# hedwig.net
KiCad netlist of a schematic drawn in EAGLE
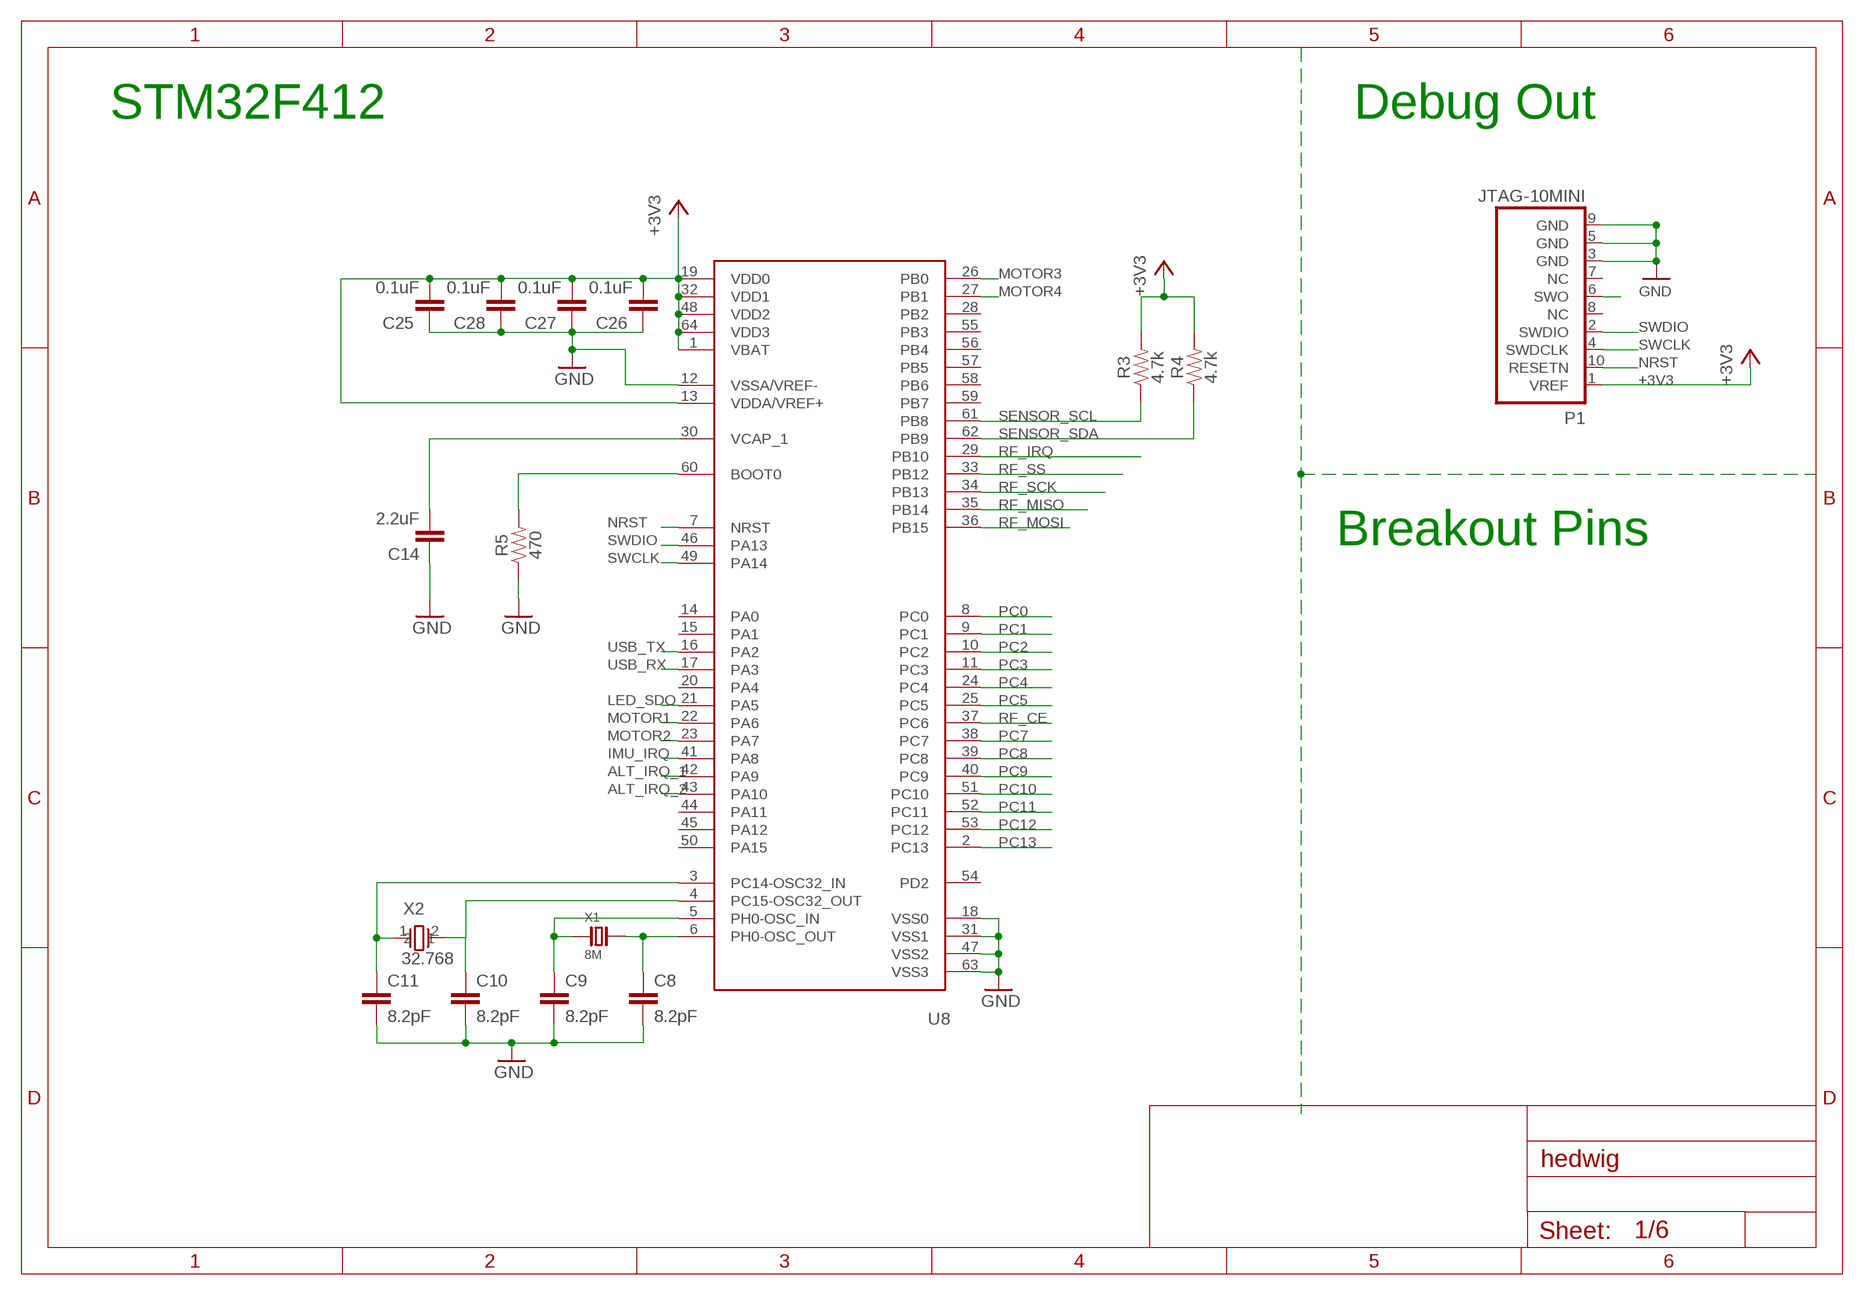
[diagram p0: schematic, sheet 1]
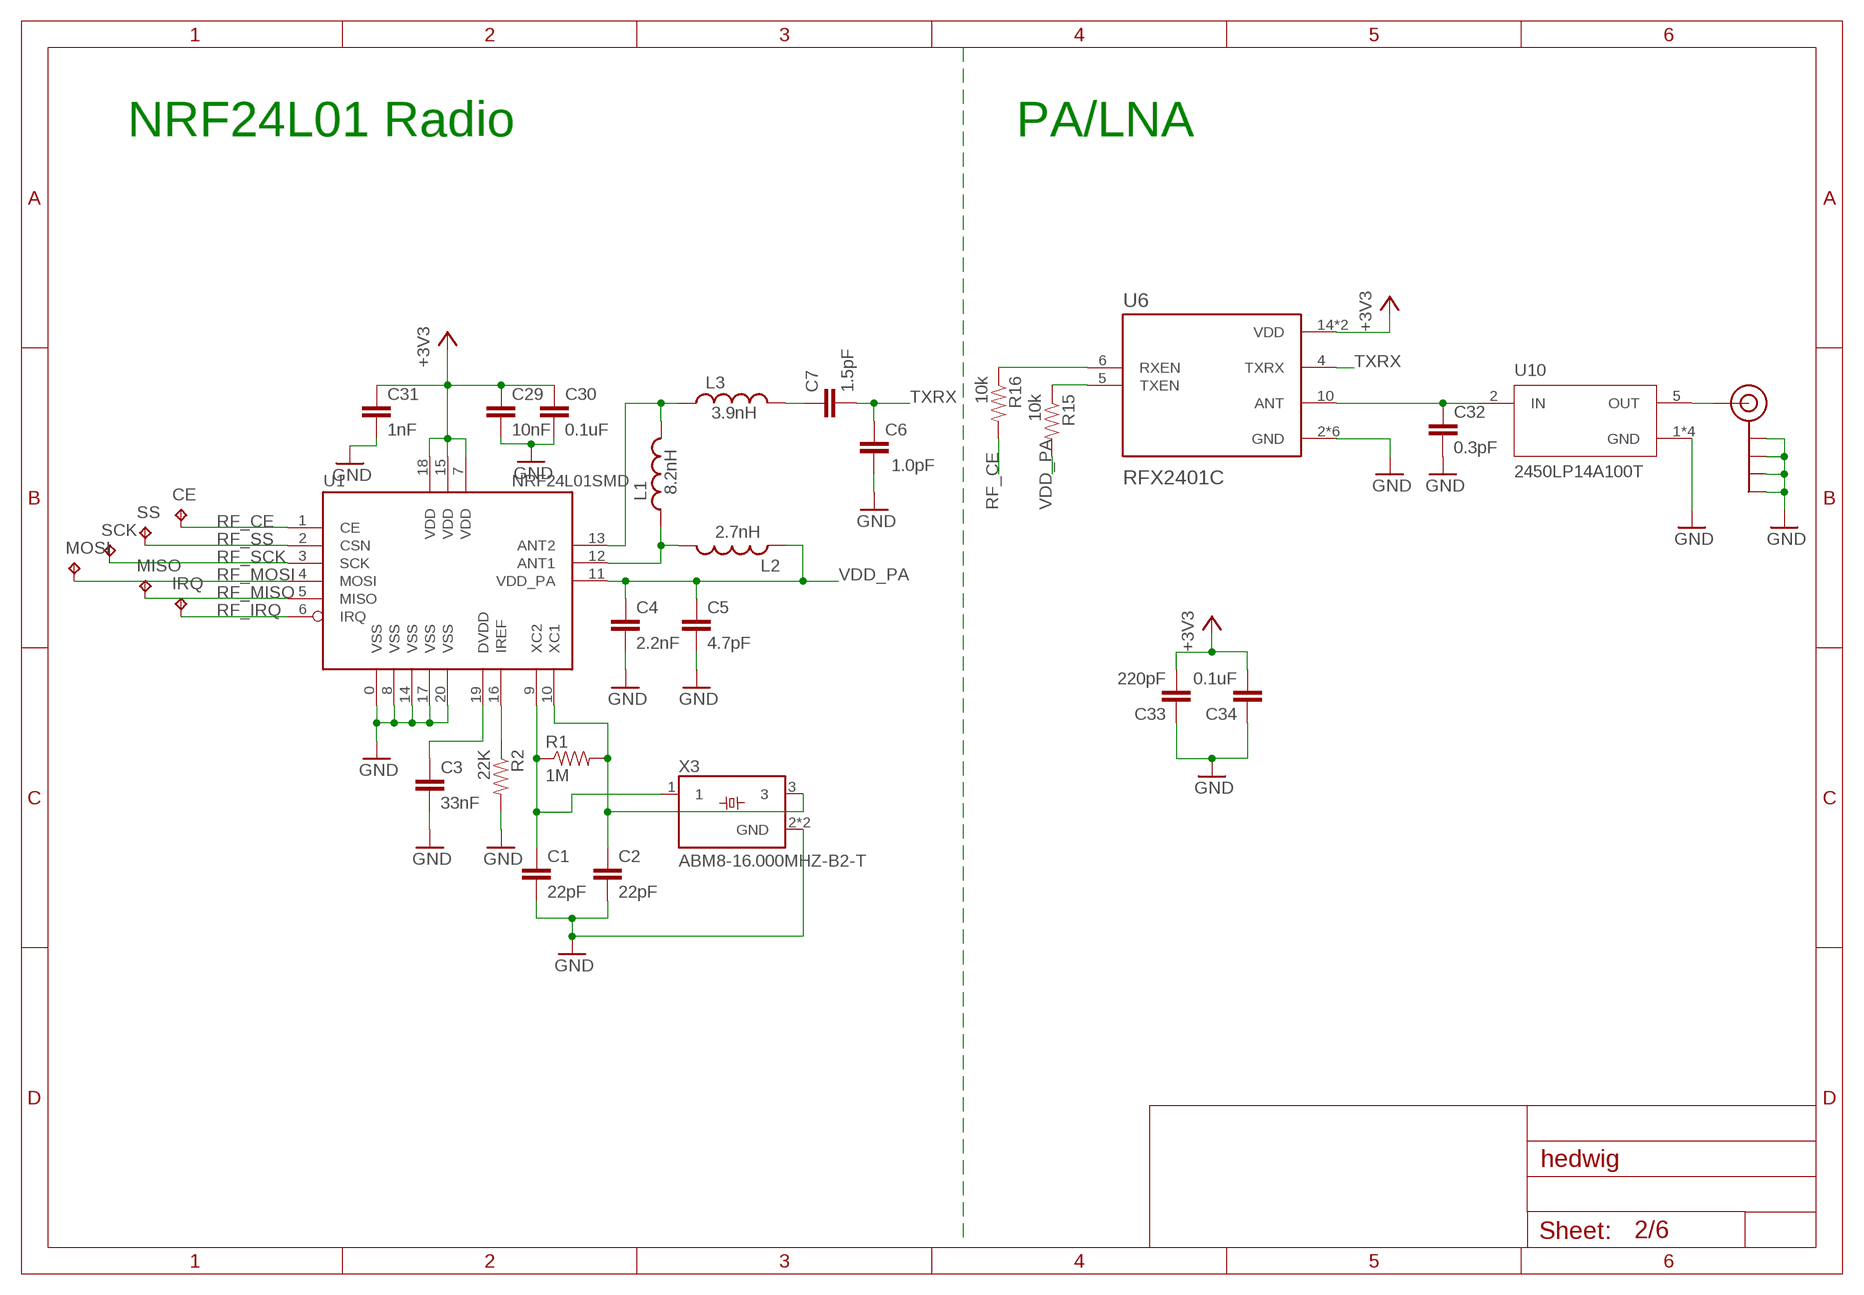
[diagram p1: schematic, sheet 2]
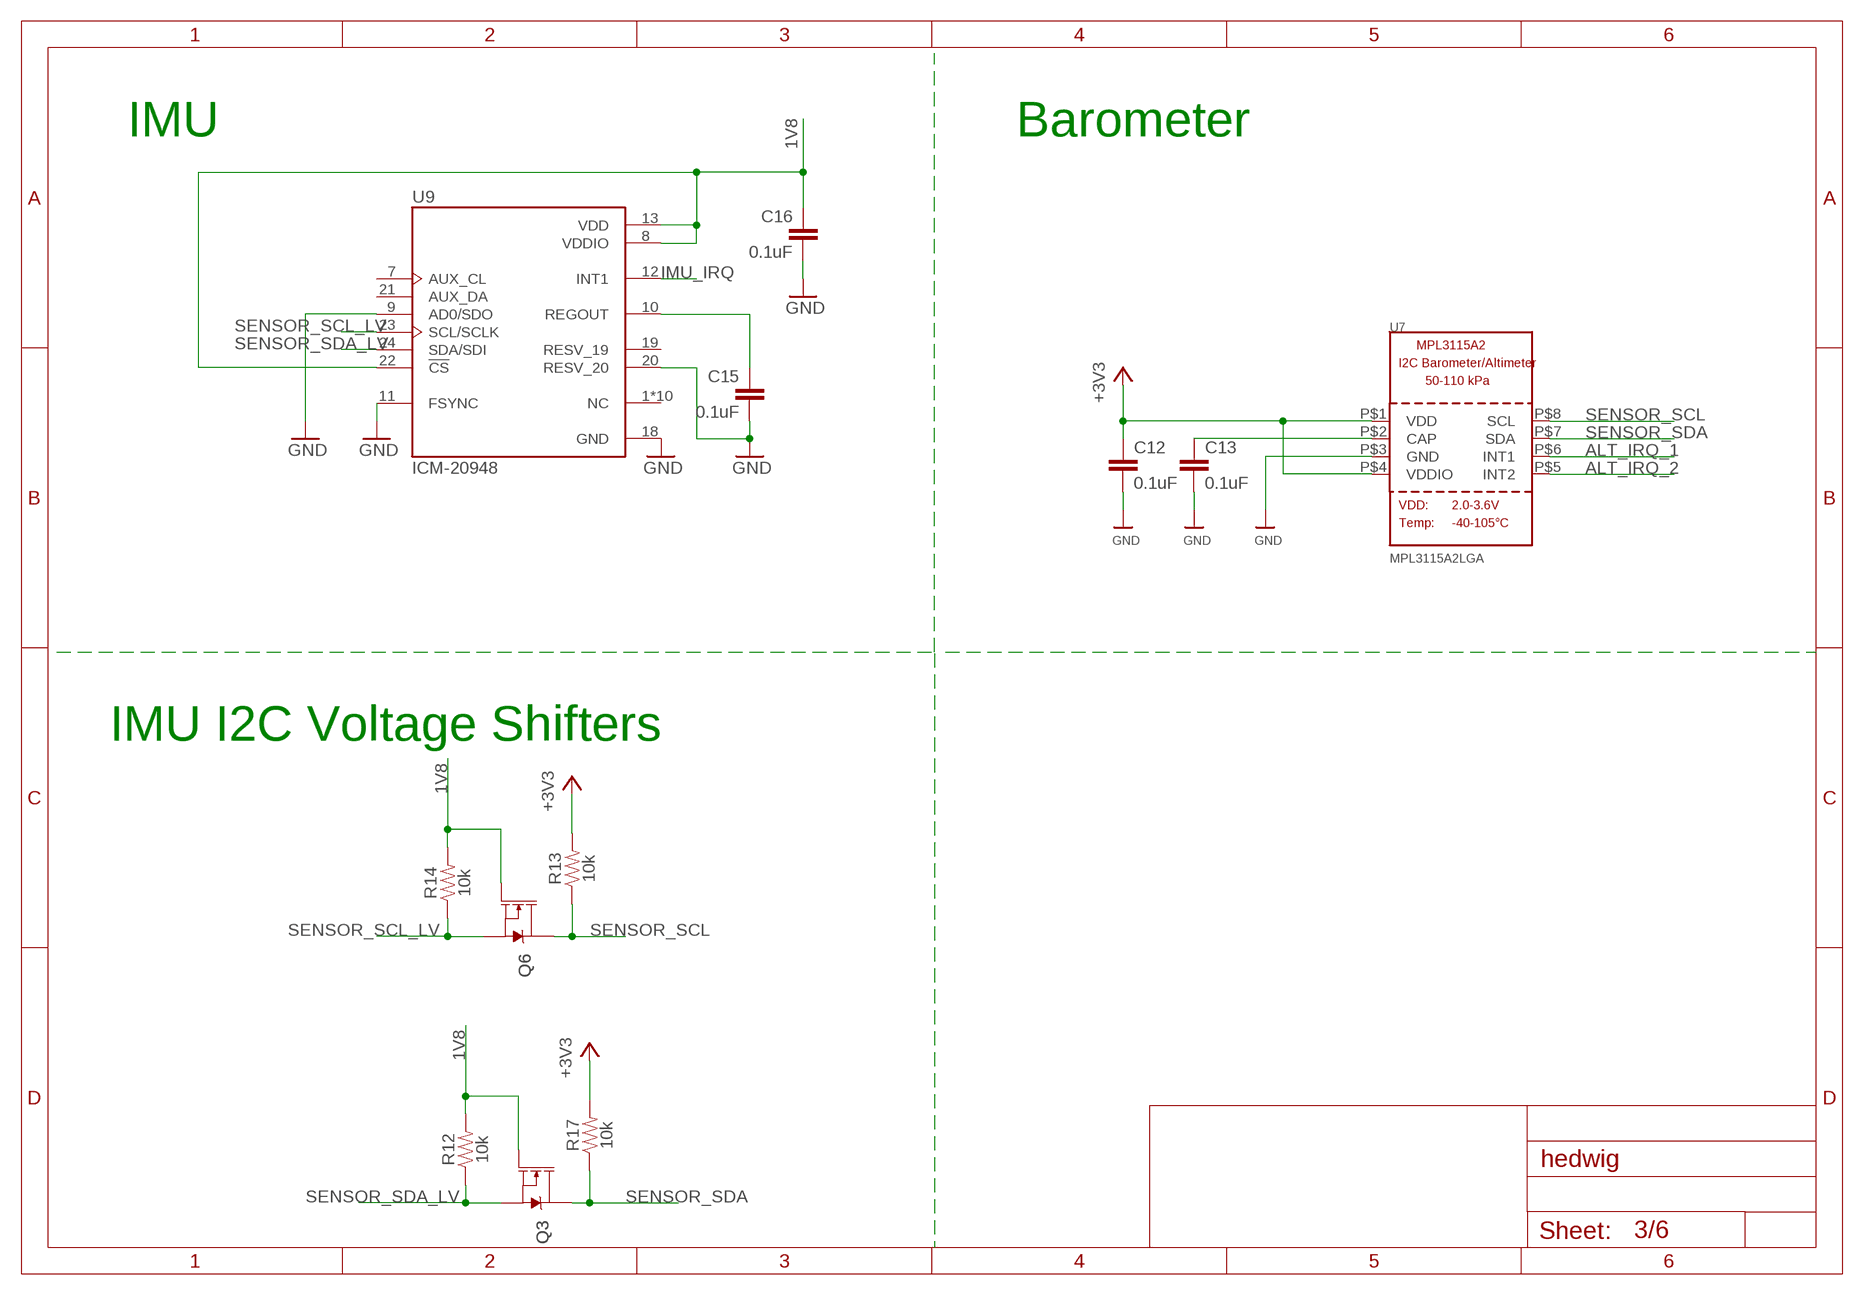
[diagram p2: schematic, sheet 3]
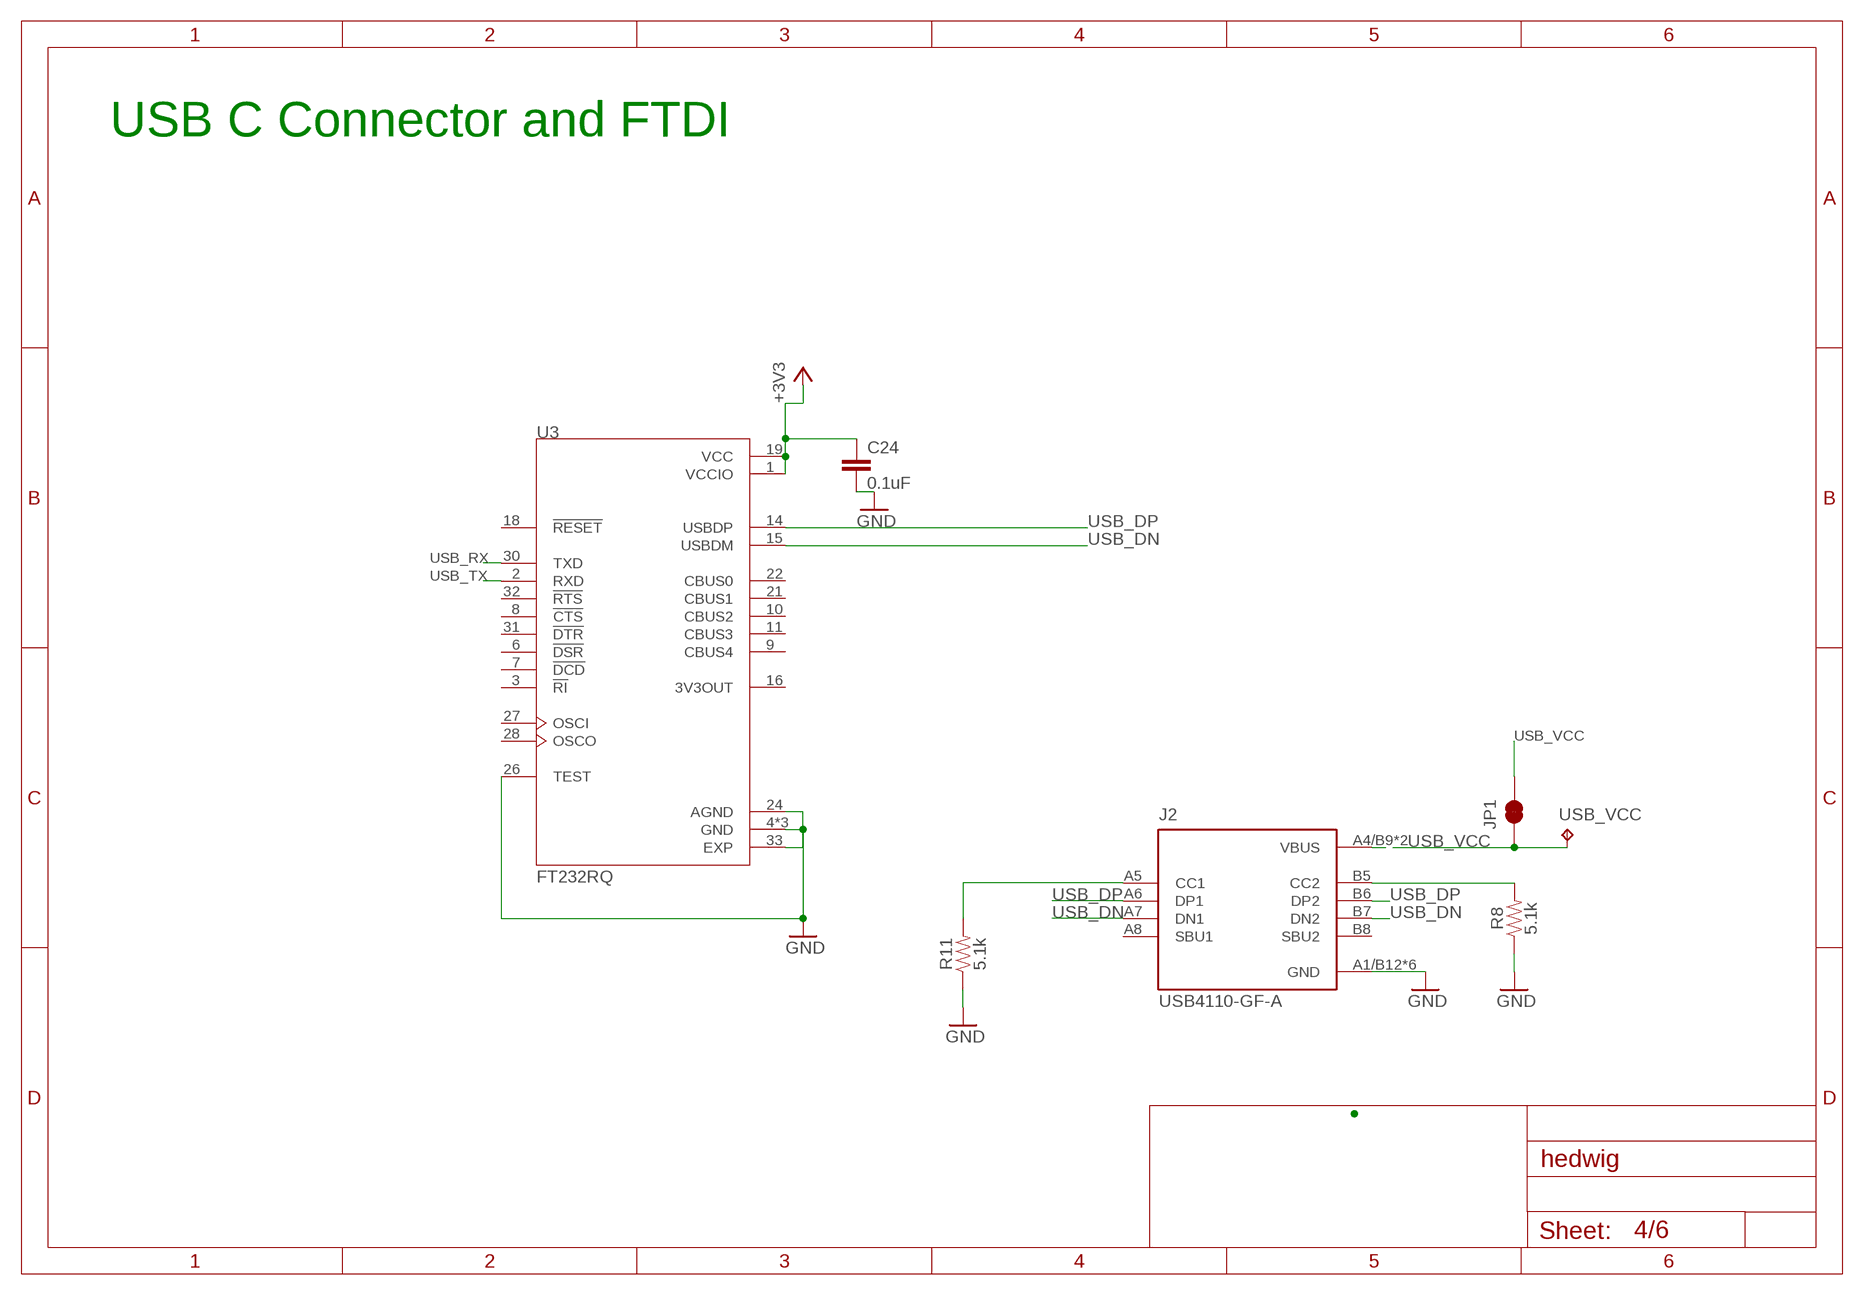
[diagram p3: schematic, sheet 4]
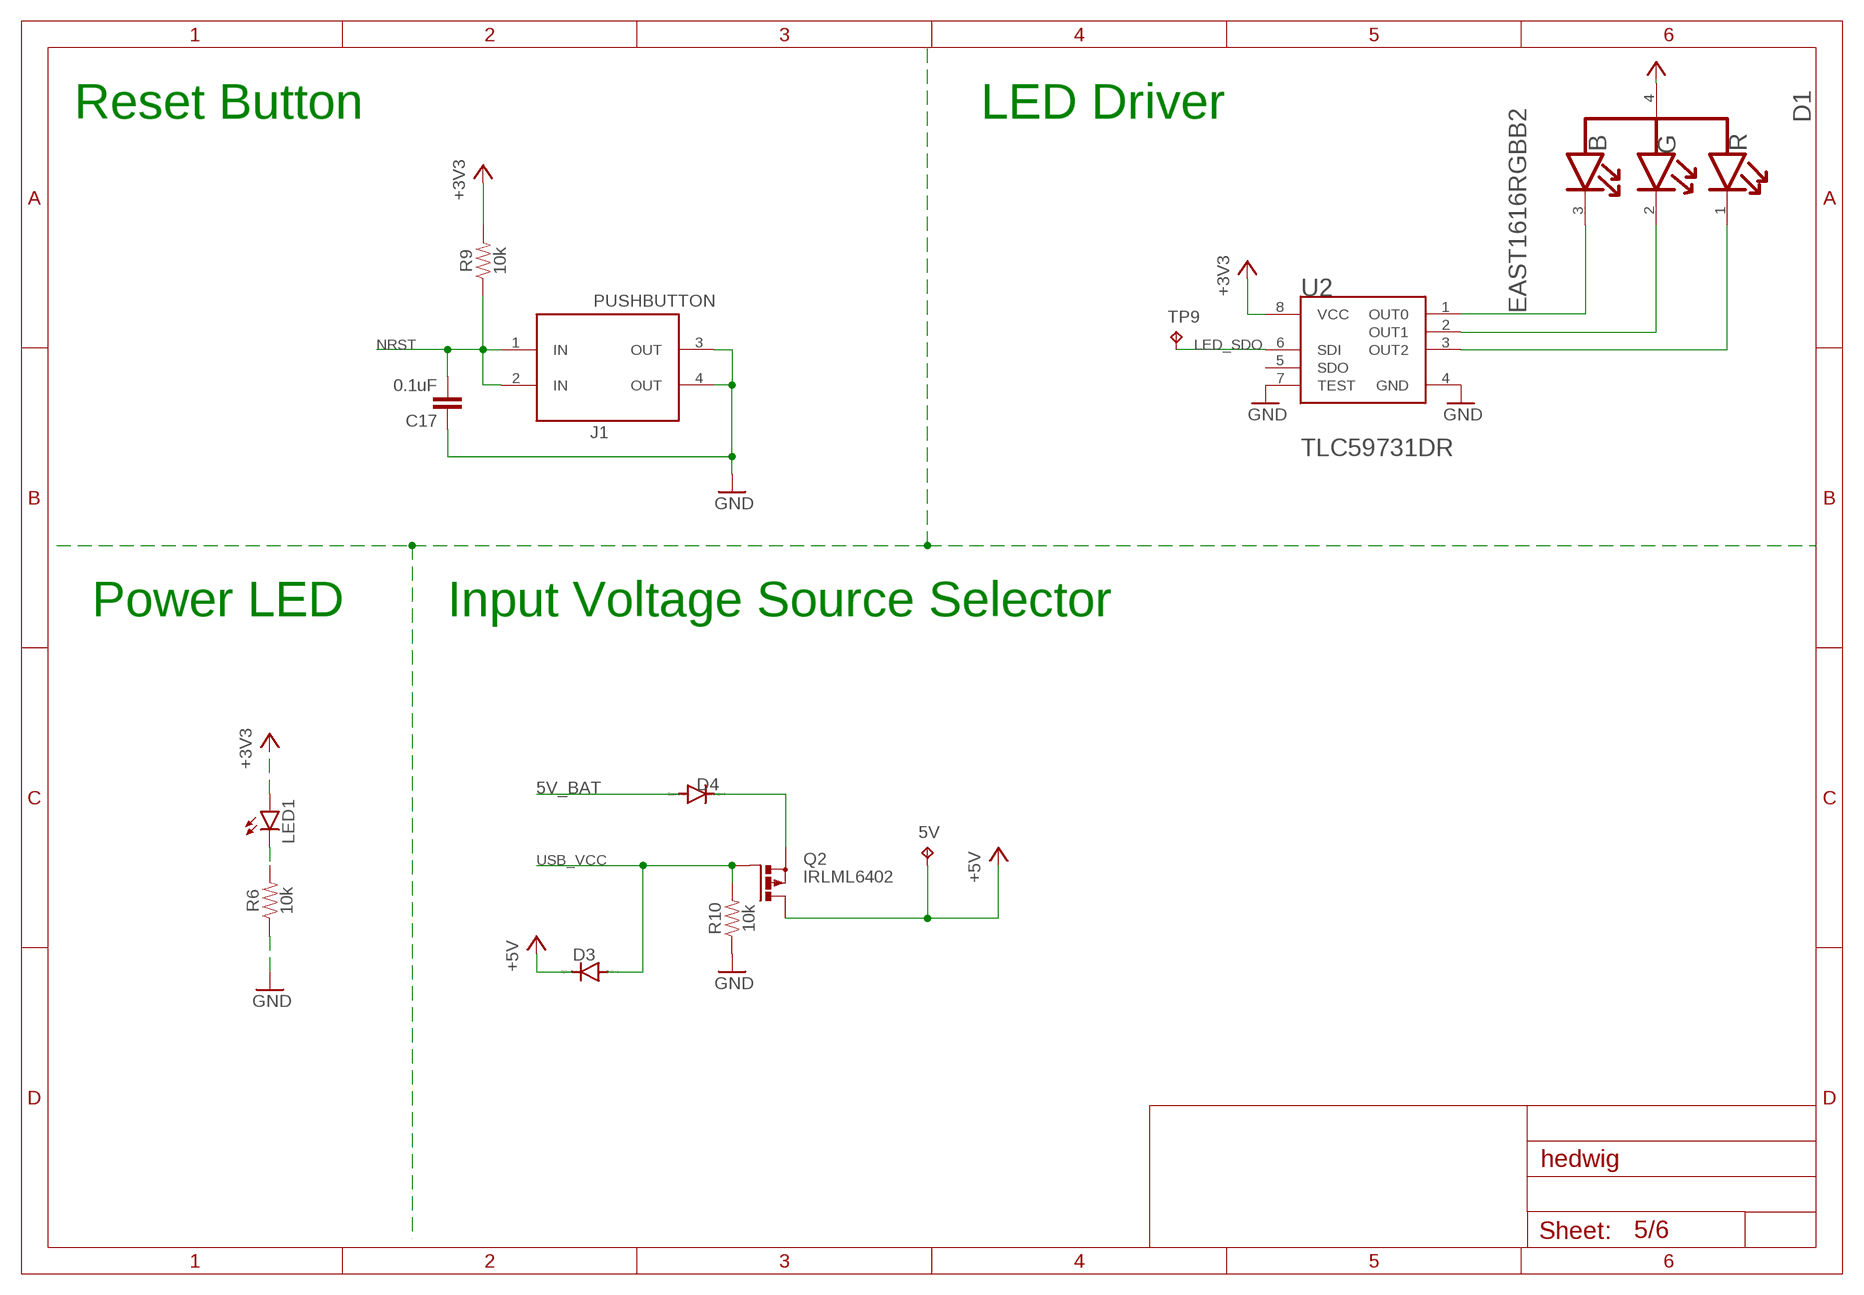
[diagram p4: schematic, sheet 5]
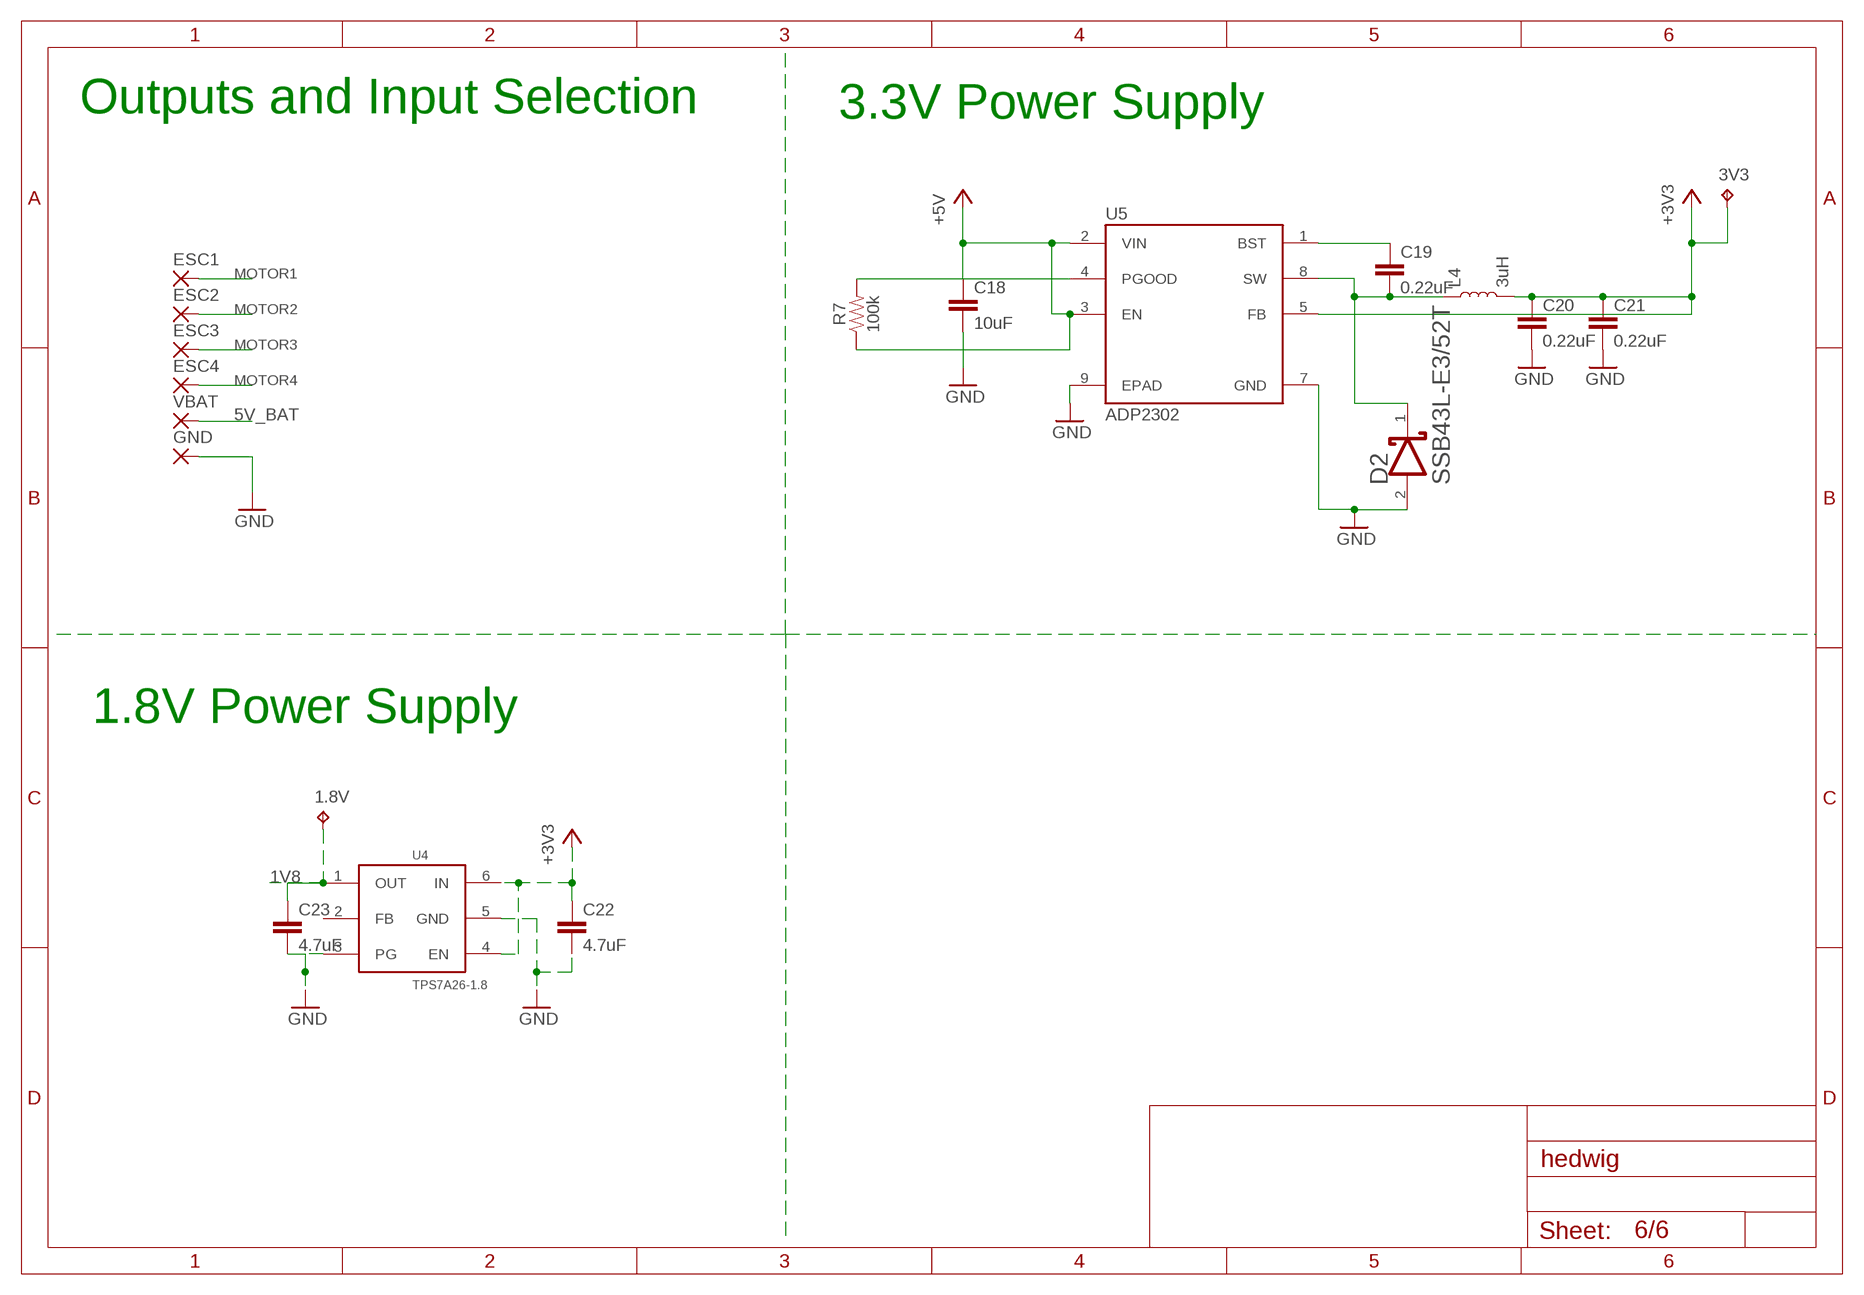
[diagram p5: schematic, sheet 6]

(export (version "E")
  (design (tool "Eeschema 10.0.6"))
  (components
    (comp (ref "5V")
      (value "TPB2,54")
      (footprint "eagle-import:B2,54")
      (libsource (lib "eagle-import") (part "TPB2,54"))
    )
    (comp (ref "C17")
      (value "0.1uF")
      (footprint "eagle-import:0603")
      (libsource (lib "eagle-import") (part "0.1UF-0603-25V-(+80/-20%)"))
    )
    (comp (ref "D1")
      (value "EVERLIGHT_EAST1616RGBB2EVERLIGHT_EAST1616RGBB2_0_0")
      (footprint "eagle-import:EVERLIGHT_EAST1616RGBB2_0")
      (fields
        (field (name "DIGIKEY_PART_NUMBER") "1080-1551-1-ND")
        (field (name "MF") "Everlight")
        (field (name "MOUSER_PART_NUMBER") "638-EAST1616RGBB2")
      )
      (libsource (lib "eagle-import") (part "EVERLIGHT_EAST1616RGBB2EVERLIGHT_EAST1616RGBB2_0_0"))
    )
    (comp (ref "D3")
      (value "DIODE_0603")
      (footprint "eagle-import:DIODE_0603")
      (libsource (lib "eagle-import") (part "DIODE_0603"))
    )
    (comp (ref "D4")
      (value "DIODE_0603")
      (footprint "eagle-import:DIODE_0603")
      (libsource (lib "eagle-import") (part "DIODE_0603"))
    )
    (comp (ref "J1")
      (value "PUSHBUTTON")
      (footprint "eagle-import:PUSH_BUTTON")
      (libsource (lib "eagle-import") (part "PUSHBUTTON"))
    )
    (comp (ref "LED1")
      (value "LEDCHIPLED_1206")
      (footprint "eagle-import:CHIPLED_1206")
      (libsource (lib "eagle-import") (part "LEDCHIPLED_1206"))
    )
    (comp (ref "Q2")
      (value "IRLML6402")
      (footprint "eagle-import:SOT-23")
      (libsource (lib "eagle-import") (part "IRLML6402"))
    )
    (comp (ref "R6")
      (value "10k")
      (footprint "eagle-import:0603")
      (libsource (lib "eagle-import") (part "10KOHM-0603-1/10W-1%"))
    )
    (comp (ref "R9")
      (value "10k")
      (footprint "eagle-import:0603")
      (libsource (lib "eagle-import") (part "1.5KOHM-0603-1/10W-1%"))
    )
    (comp (ref "R10")
      (value "10k")
      (footprint "eagle-import:0603")
      (libsource (lib "eagle-import") (part "2.49KOHM-0603-1/10W-1%"))
    )
    (comp (ref "TP9")
      (value "TPB1,27")
      (footprint "eagle-import:B1,27")
      (libsource (lib "eagle-import") (part "TPB1,27"))
    )
    (comp (ref "U2")
      (value "TEXAS_INSTRUMENTS_TLC59731DRTEXAS_INSTRUMENTS_TLC59731DR_0_0")
      (footprint "eagle-import:TEXAS_INSTRUMENTS_TLC59731DR_0")
      (fields
        (field (name "DIGIKEY_PART_NUMBER") "296-40590-1-ND")
        (field (name "MF") "Texas Instruments")
        (field (name "MOUSER_PART_NUMBER") "595-TLC59731DR")
      )
      (libsource (lib "eagle-import") (part "TEXAS_INSTRUMENTS_TLC59731DRTEXAS_INSTRUMENTS_TLC59731DR_0_0"))
    )
    (comp (ref "C8")
      (value "8.2pF")
      (footprint "eagle-import:0603")
      (libsource (lib "eagle-import") (part "CAPACITOR_0603"))
    )
    (comp (ref "C9")
      (value "8.2pF")
      (footprint "eagle-import:0603")
      (libsource (lib "eagle-import") (part "CAPACITOR_0603"))
    )
    (comp (ref "C10")
      (value "8.2pF")
      (footprint "eagle-import:0603")
      (libsource (lib "eagle-import") (part "CAPACITOR_0603"))
    )
    (comp (ref "C11")
      (value "8.2pF")
      (footprint "eagle-import:0603")
      (libsource (lib "eagle-import") (part "CAPACITOR_0603"))
    )
    (comp (ref "C14")
      (value "2.2uF")
      (footprint "eagle-import:0603")
      (libsource (lib "eagle-import") (part "0.1UF-0603-25V-(+80/-20%)"))
    )
    (comp (ref "C25")
      (value "0.1uF")
      (footprint "eagle-import:0603")
      (libsource (lib "eagle-import") (part "0.1UF-0603-25V-(+80/-20%)"))
    )
    (comp (ref "C26")
      (value "0.1uF")
      (footprint "eagle-import:0603")
      (libsource (lib "eagle-import") (part "0.1UF-0603-25V-(+80/-20%)"))
    )
    (comp (ref "C27")
      (value "0.1uF")
      (footprint "eagle-import:0603")
      (libsource (lib "eagle-import") (part "0.1UF-0603-25V-(+80/-20%)"))
    )
    (comp (ref "C28")
      (value "0.1uF")
      (footprint "eagle-import:0603")
      (libsource (lib "eagle-import") (part "0.1UF-0603-25V-(+80/-20%)"))
    )
    (comp (ref "P1")
      (value "JTAG-10MINI")
      (footprint "eagle-import:JTAG-10MINI")
      (libsource (lib "eagle-import") (part "JTAG-10MINI"))
    )
    (comp (ref "R3")
      (value "4.7k")
      (footprint "eagle-import:0603")
      (libsource (lib "eagle-import") (part "1.5KOHM-0603-1/10W-1%"))
    )
    (comp (ref "R4")
      (value "4.7k")
      (footprint "eagle-import:0603")
      (libsource (lib "eagle-import") (part "1.5KOHM-0603-1/10W-1%"))
    )
    (comp (ref "R5")
      (value "470")
      (footprint "eagle-import:0603")
      (libsource (lib "eagle-import") (part "1.5KOHM-0603-1/10W-1%"))
    )
    (comp (ref "U8")
      (value "STM32F412RE-S")
      (footprint "eagle-import:QFP50P1200X1200X160-64N")
      (libsource (lib "eagle-import") (part "STM32F412RE-S"))
    )
    (comp (ref "X1")
      (value "8M")
      (footprint "eagle-import:NDK-NX3225GD")
      (libsource (lib "eagle-import") (part "CRYSTAL-NX3225GD"))
    )
    (comp (ref "X2")
      (value "32.768")
      (footprint "eagle-import:NDK_NX3215SA-32.768K-STD-MUA-8_0")
      (libsource (lib "eagle-import") (part "NX32"))
    )
    (comp (ref "C24")
      (value "0.1uF")
      (footprint "eagle-import:0603")
      (libsource (lib "eagle-import") (part "0.22UF-0603-25V-10%"))
    )
    (comp (ref "J2")
      (value "USB4110-GF-A")
      (footprint "eagle-import:GCT_USB4110-GF-A")
      (fields (field (name "MF") "GCT"))
      (libsource (lib "eagle-import") (part "USB4110-GF-A"))
    )
    (comp (ref "JP1")
      (value "JUMPER-SMT_2_NC_TRACE_SILK")
      (footprint "eagle-import:SMT-JUMPER_2_NC_TRACE_SILK")
      (libsource (lib "eagle-import") (part "JUMPER-SMT_2_NC_TRACE_SILK"))
    )
    (comp (ref "R8")
      (value "5.1k")
      (footprint "eagle-import:0603")
      (libsource (lib "eagle-import") (part "5.1KOHM5.1KOHM-0603-1/10W-1%"))
    )
    (comp (ref "R11")
      (value "5.1k")
      (footprint "eagle-import:0603")
      (libsource (lib "eagle-import") (part "5.1KOHM5.1KOHM-0603-1/10W-1%"))
    )
    (comp (ref "U3")
      (value "FT232RQ")
      (footprint "eagle-import:QFN50P500X500X90-33N")
      (fields (field (name "MF") "FTDI, Future"))
      (libsource (lib "eagle-import") (part "FT232RQ"))
    )
    (comp (ref "USB_VCC")
      (value "TPB2,54")
      (footprint "eagle-import:B2,54")
      (libsource (lib "eagle-import") (part "TPB2,54"))
    )
    (comp (ref "C12")
      (value "0.1uF")
      (footprint "eagle-import:0603")
      (libsource (lib "eagle-import") (part "CAPACITOR_0603"))
    )
    (comp (ref "C13")
      (value "0.1uF")
      (footprint "eagle-import:0603")
      (libsource (lib "eagle-import") (part "CAPACITOR_0603"))
    )
    (comp (ref "C15")
      (value "0.1uF")
      (footprint "eagle-import:0603-CAP")
      (libsource (lib "eagle-import") (part "0.1UF-25V(+80/-20%)(0603)"))
    )
    (comp (ref "C16")
      (value "0.1uF")
      (footprint "eagle-import:0603-CAP")
      (libsource (lib "eagle-import") (part "0.1UF-25V(+80/-20%)(0603)"))
    )
    (comp (ref "Q3")
      (value "20V/0.2A/8MHz/1.2Ω/1Vth")
      (footprint "eagle-import:SOT-416FL")
      (libsource (lib "eagle-import") (part "MOSFET-NCH-RE1C002UN"))
    )
    (comp (ref "Q6")
      (value "20V/0.2A/8MHz/1.2Ω/1Vth")
      (footprint "eagle-import:SOT-416FL")
      (libsource (lib "eagle-import") (part "MOSFET-NCH-RE1C002UN"))
    )
    (comp (ref "R12")
      (value "10k")
      (footprint "eagle-import:0603")
      (libsource (lib "eagle-import") (part "2.49KOHM-0603-1/10W-1%"))
    )
    (comp (ref "R13")
      (value "10k")
      (footprint "eagle-import:0603")
      (libsource (lib "eagle-import") (part "2.49KOHM-0603-1/10W-1%"))
    )
    (comp (ref "R14")
      (value "10k")
      (footprint "eagle-import:0603")
      (libsource (lib "eagle-import") (part "2.49KOHM-0603-1/10W-1%"))
    )
    (comp (ref "R17")
      (value "10k")
      (footprint "eagle-import:0603")
      (libsource (lib "eagle-import") (part "2.49KOHM-0603-1/10W-1%"))
    )
    (comp (ref "U7")
      (value "MPL3115A2LGA")
      (footprint "eagle-import:LGA8")
      (libsource (lib "eagle-import") (part "MPL3115A2LGA"))
    )
    (comp (ref "U9")
      (value "ICM-20948")
      (footprint "eagle-import:QFN40P300X300X105-24N")
      (fields (field (name "DIGI-KEY_PART_NUMBER") "1428-1123-1-ND") (field (name "MF") "TDK InvenSense"))
      (libsource (lib "eagle-import") (part "ICM-20948"))
    )
    (comp (ref "1.8V")
      (value "TPB2,54")
      (footprint "eagle-import:B2,54")
      (libsource (lib "eagle-import") (part "TPB2,54"))
    )
    (comp (ref "3V3")
      (value "TPB2,54")
      (footprint "eagle-import:B2,54")
      (libsource (lib "eagle-import") (part "TPB2,54"))
    )
    (comp (ref "C18")
      (value "10uF")
      (footprint "eagle-import:0603")
      (libsource (lib "eagle-import") (part "10UF-0603-6.3V-20%"))
    )
    (comp (ref "C19")
      (value "0.22uF")
      (footprint "eagle-import:0603")
      (libsource (lib "eagle-import") (part "0.22UF-0603-25V-10%"))
    )
    (comp (ref "C20")
      (value "0.22uF")
      (footprint "eagle-import:0603")
      (libsource (lib "eagle-import") (part "0.22UF-0603-25V-10%"))
    )
    (comp (ref "C21")
      (value "0.22uF")
      (footprint "eagle-import:0603")
      (libsource (lib "eagle-import") (part "0.22UF-0603-25V-10%"))
    )
    (comp (ref "C22")
      (value "4.7uF")
      (footprint "eagle-import:0603")
      (libsource (lib "eagle-import") (part "4.7UF-0603-35V-(20%)"))
    )
    (comp (ref "C23")
      (value "4.7uF")
      (footprint "eagle-import:0603")
      (libsource (lib "eagle-import") (part "4.7UF-0603-35V-(20%)"))
    )
    (comp (ref "D2")
      (value "SSB43L")
      (footprint "eagle-import:VISHAY_SSB43L-E3-52T_0")
      (fields
        (field (name "DIGIKEY_PART_NUMBER") "SSB43L-E3/52TGICT-ND")
        (field (name "MF") "Vishay")
        (field (name "MOUSER_PART_NUMBER") "625-SSB43L-E3")
      )
      (libsource (lib "eagle-import") (part "VISHAY_SSB43L-E3-52TVISHAY_SSB43L-E3-52T_0_0"))
    )
    (comp (ref "ESC1")
      (value "SMD2")
      (footprint "eagle-import:SMD1,27-2,54")
      (libsource (lib "eagle-import") (part "SMD2"))
    )
    (comp (ref "ESC2")
      (value "SMD2")
      (footprint "eagle-import:SMD1,27-2,54")
      (libsource (lib "eagle-import") (part "SMD2"))
    )
    (comp (ref "ESC3")
      (value "SMD2")
      (footprint "eagle-import:SMD1,27-2,54")
      (libsource (lib "eagle-import") (part "SMD2"))
    )
    (comp (ref "ESC4")
      (value "SMD2")
      (footprint "eagle-import:SMD1,27-2,54")
      (libsource (lib "eagle-import") (part "SMD2"))
    )
    (comp (ref "GND")
      (value "2,54/1,0")
      (footprint "eagle-import:2,54_1,0")
      (libsource (lib "eagle-import") (part "2,54/1,0"))
    )
    (comp (ref "L4")
      (value "3uH")
      (footprint "eagle-import:REG_INDUCTOR")
      (libsource (lib "eagle-import") (part "REG_INDUCTOR"))
    )
    (comp (ref "R7")
      (value "100k")
      (footprint "eagle-import:0603")
      (libsource (lib "eagle-import") (part "100KOHM-0603-1/10W-1%"))
    )
    (comp (ref "U4")
      (value "TPS7A26-1.8")
      (footprint "eagle-import:WSON")
      (libsource (lib "eagle-import") (part "TPS7A26-1.8"))
    )
    (comp (ref "U5")
      (value "ADP2302")
      (footprint "eagle-import:SOIC127P600X175-9N")
      (libsource (lib "eagle-import") (part "ADP2302"))
    )
    (comp (ref "VBAT")
      (value "2,54/1,0")
      (footprint "eagle-import:2,54_1,0")
      (libsource (lib "eagle-import") (part "2,54/1,0"))
    )
    (comp (ref "C1")
      (value "22pF")
      (footprint "eagle-import:C0402")
      (libsource (lib "eagle-import") (part "CAP0402"))
    )
    (comp (ref "C2")
      (value "22pF")
      (footprint "eagle-import:C0402")
      (libsource (lib "eagle-import") (part "CAP0402"))
    )
    (comp (ref "C3")
      (value "33nF")
      (footprint "eagle-import:C0402")
      (libsource (lib "eagle-import") (part "CAP0402"))
    )
    (comp (ref "C4")
      (value "2.2nF")
      (footprint "eagle-import:C0402")
      (libsource (lib "eagle-import") (part "CAP0402"))
    )
    (comp (ref "C5")
      (value "4.7pF")
      (footprint "eagle-import:C0402")
      (libsource (lib "eagle-import") (part "CAP0402"))
    )
    (comp (ref "C6")
      (value "1.0pF")
      (footprint "eagle-import:C0402")
      (libsource (lib "eagle-import") (part "CAP0402"))
    )
    (comp (ref "C7")
      (value "1.5pF")
      (footprint "eagle-import:C0402")
      (libsource (lib "eagle-import") (part "CAP0402"))
    )
    (comp (ref "C29")
      (value "10nF")
      (footprint "eagle-import:C0402")
      (libsource (lib "eagle-import") (part "CAP0402"))
    )
    (comp (ref "C30")
      (value "0.1uF")
      (footprint "eagle-import:C0402")
      (libsource (lib "eagle-import") (part "CAP0402"))
    )
    (comp (ref "C31")
      (value "1nF")
      (footprint "eagle-import:C0402")
      (libsource (lib "eagle-import") (part "CAP0402"))
    )
    (comp (ref "C32")
      (value "0.3pF")
      (footprint "eagle-import:C0402")
      (libsource (lib "eagle-import") (part "CAP0402"))
    )
    (comp (ref "C33")
      (value "220pF")
      (footprint "eagle-import:C0402")
      (libsource (lib "eagle-import") (part "CAP0402"))
    )
    (comp (ref "C34")
      (value "0.1uF")
      (footprint "eagle-import:C0402")
      (libsource (lib "eagle-import") (part "CAP0402"))
    )
    (comp (ref "CE")
      (value "TPB1,27")
      (footprint "eagle-import:B1,27")
      (libsource (lib "eagle-import") (part "TPB1,27"))
    )
    (comp (ref "IRQ")
      (value "TPB1,27")
      (footprint "eagle-import:B1,27")
      (libsource (lib "eagle-import") (part "TPB1,27"))
    )
    (comp (ref "J3")
      (value "SMA_EDGE")
      (footprint "eagle-import:SMA-EDGE")
      (libsource (lib "eagle-import") (part "SMA_EDGE"))
    )
    (comp (ref "L1")
      (value "8.2nH")
      (footprint "eagle-import:C0402")
      (libsource (lib "eagle-import") (part "INDUCTOR0402"))
    )
    (comp (ref "L2")
      (value "2.7nH")
      (footprint "eagle-import:C0402")
      (libsource (lib "eagle-import") (part "INDUCTOR0402"))
    )
    (comp (ref "L3")
      (value "3.9nH")
      (footprint "eagle-import:C0402")
      (libsource (lib "eagle-import") (part "INDUCTOR0402"))
    )
    (comp (ref "MISO")
      (value "TPB1,27")
      (footprint "eagle-import:B1,27")
      (libsource (lib "eagle-import") (part "TPB1,27"))
    )
    (comp (ref "MOSI")
      (value "TPB1,27")
      (footprint "eagle-import:B1,27")
      (libsource (lib "eagle-import") (part "TPB1,27"))
    )
    (comp (ref "R1")
      (value "1M")
      (footprint "eagle-import:C0402")
      (libsource (lib "eagle-import") (part "RESISTOR0402"))
    )
    (comp (ref "R2")
      (value "22K")
      (footprint "eagle-import:C0402")
      (libsource (lib "eagle-import") (part "RESISTOR0402"))
    )
    (comp (ref "R15")
      (value "10k")
      (footprint "eagle-import:C0402")
      (libsource (lib "eagle-import") (part "RESISTOR0402"))
    )
    (comp (ref "R16")
      (value "10k")
      (footprint "eagle-import:C0402")
      (libsource (lib "eagle-import") (part "RESISTOR0402"))
    )
    (comp (ref "SCK")
      (value "TPB1,27")
      (footprint "eagle-import:B1,27")
      (libsource (lib "eagle-import") (part "TPB1,27"))
    )
    (comp (ref "SS")
      (value "TPB1,27")
      (footprint "eagle-import:B1,27")
      (libsource (lib "eagle-import") (part "TPB1,27"))
    )
    (comp (ref "U1")
      (value "NRF24L01SMD")
      (footprint "eagle-import:QFN20")
      (libsource (lib "eagle-import") (part "NRF24L01SMD"))
    )
    (comp (ref "U6")
      (value "RFX2401C")
      (footprint "eagle-import:QFN50P300X300X60-17N")
      (fields (field (name "MF") "Skyworks Solutions"))
      (libsource (lib "eagle-import") (part "RFX2401C"))
    )
    (comp (ref "U10")
      (value "2450LP14A100T")
      (footprint "eagle-import:ICCAF50P160X80X70-6N")
      (fields (field (name "MF") "Johanson Technology"))
      (libsource (lib "eagle-import") (part "2450LP14A100T"))
    )
    (comp (ref "X3")
      (value "ABM8-16.000MHZ-B2-T")
      (footprint "eagle-import:OSCSC320X250X100N")
      (fields (field (name "MF") "Abracon"))
      (libsource (lib "eagle-import") (part "ABM8-16.000MHZ-B2-T"))
    )
  )
  (nets
    (net (code "1") (name "+3V3") (class "Default")
      (node (ref "3V3") (pin "TP") (pinfunction "TP_TP") (pintype "input"))
      (node (ref "C12") (pin "1") (pinfunction "1_1") (pintype "passive"))
      (node (ref "C20") (pin "1") (pinfunction "1_1") (pintype "passive"))
      (node (ref "C21") (pin "1") (pinfunction "1_1") (pintype "passive"))
      (node (ref "C22") (pin "1") (pinfunction "1_1") (pintype "passive"))
      (node (ref "C24") (pin "1") (pinfunction "1_1") (pintype "passive"))
      (node (ref "C25") (pin "2") (pinfunction "2_2") (pintype "passive"))
      (node (ref "C26") (pin "2") (pinfunction "2_2") (pintype "passive"))
      (node (ref "C27") (pin "2") (pinfunction "2_2") (pintype "passive"))
      (node (ref "C28") (pin "2") (pinfunction "2_2") (pintype "passive"))
      (node (ref "C29") (pin "1") (pinfunction "1_1") (pintype "passive"))
      (node (ref "C30") (pin "1") (pinfunction "1_1") (pintype "passive"))
      (node (ref "C31") (pin "1") (pinfunction "1_1") (pintype "passive"))
      (node (ref "C33") (pin "2") (pinfunction "2_2") (pintype "passive"))
      (node (ref "C34") (pin "2") (pinfunction "2_2") (pintype "passive"))
      (node (ref "D1") (pin "4") (pinfunction "COMMON_ANODE_4") (pintype "passive"))
      (node (ref "L4") (pin "@2") (pinfunction "2_@2") (pintype "passive"))
      (node (ref "LED1") (pin "A") (pinfunction "A_A") (pintype "passive"))
      (node (ref "P1") (pin "1") (pinfunction "VREF_1") (pintype "passive"))
      (node (ref "R13") (pin "2") (pinfunction "2_2") (pintype "passive"))
      (node (ref "R17") (pin "2") (pinfunction "2_2") (pintype "passive"))
      (node (ref "R3") (pin "2") (pinfunction "2_2") (pintype "passive"))
      (node (ref "R4") (pin "2") (pinfunction "2_2") (pintype "passive"))
      (node (ref "R9") (pin "2") (pinfunction "2_2") (pintype "passive"))
      (node (ref "U1") (pin "15") (pinfunction "VDD_15") (pintype "power_in"))
      (node (ref "U1") (pin "18") (pinfunction "VDD_18") (pintype "power_in"))
      (node (ref "U1") (pin "7") (pinfunction "VDD_7") (pintype "power_in"))
      (node (ref "U2") (pin "8") (pinfunction "VCC_8") (pintype "bidirectional"))
      (node (ref "U3") (pin "1") (pinfunction "VCCIO_1") (pintype "power_in"))
      (node (ref "U3") (pin "19") (pinfunction "VCC_19") (pintype "power_in"))
      (node (ref "U4") (pin "4") (pinfunction "EN_4") (pintype "bidirectional"))
      (node (ref "U4") (pin "6") (pinfunction "IN_6") (pintype "bidirectional"))
      (node (ref "U5") (pin "5") (pinfunction "FB_5") (pintype "input"))
      (node (ref "U6") (pin "14") (pinfunction "VDD_14") (pintype "power_in"))
      (node (ref "U6") (pin "16") (pinfunction "VDD_16") (pintype "power_in"))
      (node (ref "U7") (pin "P$1") (pinfunction "VDD_P$1") (pintype "power_in"))
      (node (ref "U7") (pin "P$4") (pinfunction "VDDIO_P$4") (pintype "power_in"))
      (node (ref "U8") (pin "1") (pinfunction "VBAT_1") (pintype "bidirectional"))
      (node (ref "U8") (pin "13") (pinfunction "VDDA/VREF+_13") (pintype "bidirectional"))
      (node (ref "U8") (pin "19") (pinfunction "VDD0_19") (pintype "bidirectional"))
      (node (ref "U8") (pin "32") (pinfunction "VDD1_32") (pintype "bidirectional"))
      (node (ref "U8") (pin "48") (pinfunction "VDD2_48") (pintype "bidirectional"))
      (node (ref "U8") (pin "64") (pinfunction "VDD3_64") (pintype "bidirectional"))
    )
    (net (code "2") (name "+5V") (class "Default")
      (node (ref "5V") (pin "TP") (pinfunction "TP_TP") (pintype "input"))
      (node (ref "C18") (pin "1") (pinfunction "1_1") (pintype "passive"))
      (node (ref "D3") (pin "C") (pinfunction "C_C") (pintype "passive"))
      (node (ref "Q2") (pin "P3") (pinfunction "D_P3") (pintype "passive"))
      (node (ref "R7") (pin "1") (pinfunction "1_1") (pintype "passive"))
      (node (ref "U5") (pin "2") (pinfunction "VIN_2") (pintype "input"))
      (node (ref "U5") (pin "3") (pinfunction "EN_3") (pintype "input"))
    )
    (net (code "3") (name "1V8") (class "Default")
      (node (ref "1.8V") (pin "TP") (pinfunction "TP_TP") (pintype "input"))
      (node (ref "C16") (pin "1") (pinfunction "1_1") (pintype "passive"))
      (node (ref "C23") (pin "1") (pinfunction "1_1") (pintype "passive"))
      (node (ref "Q3") (pin "1") (pinfunction "G_1") (pintype "bidirectional"))
      (node (ref "Q6") (pin "1") (pinfunction "G_1") (pintype "bidirectional"))
      (node (ref "R12") (pin "2") (pinfunction "2_2") (pintype "passive"))
      (node (ref "R14") (pin "2") (pinfunction "2_2") (pintype "passive"))
      (node (ref "U4") (pin "1") (pinfunction "OUT_1") (pintype "bidirectional"))
      (node (ref "U9") (pin "13") (pinfunction "VDD_13") (pintype "power_in"))
      (node (ref "U9") (pin "22") (pinfunction "~{CS}_22") (pintype "input"))
      (node (ref "U9") (pin "8") (pinfunction "VDDIO_8") (pintype "power_in"))
    )
    (net (code "4") (name "5V_BAT") (class "Default")
      (node (ref "D4") (pin "A") (pinfunction "A_A") (pintype "passive"))
      (node (ref "VBAT") (pin "1") (pinfunction "P_1") (pintype "passive"))
    )
    (net (code "5") (name "ALT_IRQ_1") (class "Default")
      (node (ref "U7") (pin "P$6") (pinfunction "INT1_P$6") (pintype "output"))
      (node (ref "U8") (pin "42") (pinfunction "PA9_42") (pintype "bidirectional"))
    )
    (net (code "6") (name "ALT_IRQ_2") (class "Default")
      (node (ref "U7") (pin "P$5") (pinfunction "INT2_P$5") (pintype "output"))
      (node (ref "U8") (pin "43") (pinfunction "PA10_43") (pintype "bidirectional"))
    )
    (net (code "7") (name "GND") (class "Default")
      (node (ref "C1") (pin "2") (pinfunction "2_2") (pintype "passive"))
      (node (ref "C10") (pin "2") (pinfunction "2_2") (pintype "passive"))
      (node (ref "C11") (pin "2") (pinfunction "2_2") (pintype "passive"))
      (node (ref "C12") (pin "2") (pinfunction "2_2") (pintype "passive"))
      (node (ref "C13") (pin "2") (pinfunction "2_2") (pintype "passive"))
      (node (ref "C14") (pin "1") (pinfunction "1_1") (pintype "passive"))
      (node (ref "C15") (pin "2") (pinfunction "2_2") (pintype "passive"))
      (node (ref "C16") (pin "2") (pinfunction "2_2") (pintype "passive"))
      (node (ref "C17") (pin "1") (pinfunction "1_1") (pintype "passive"))
      (node (ref "C18") (pin "2") (pinfunction "2_2") (pintype "passive"))
      (node (ref "C2") (pin "2") (pinfunction "2_2") (pintype "passive"))
      (node (ref "C20") (pin "2") (pinfunction "2_2") (pintype "passive"))
      (node (ref "C21") (pin "2") (pinfunction "2_2") (pintype "passive"))
      (node (ref "C22") (pin "2") (pinfunction "2_2") (pintype "passive"))
      (node (ref "C23") (pin "2") (pinfunction "2_2") (pintype "passive"))
      (node (ref "C24") (pin "2") (pinfunction "2_2") (pintype "passive"))
      (node (ref "C25") (pin "1") (pinfunction "1_1") (pintype "passive"))
      (node (ref "C26") (pin "1") (pinfunction "1_1") (pintype "passive"))
      (node (ref "C27") (pin "1") (pinfunction "1_1") (pintype "passive"))
      (node (ref "C28") (pin "1") (pinfunction "1_1") (pintype "passive"))
      (node (ref "C29") (pin "2") (pinfunction "2_2") (pintype "passive"))
      (node (ref "C3") (pin "2") (pinfunction "2_2") (pintype "passive"))
      (node (ref "C30") (pin "2") (pinfunction "2_2") (pintype "passive"))
      (node (ref "C31") (pin "2") (pinfunction "2_2") (pintype "passive"))
      (node (ref "C32") (pin "2") (pinfunction "2_2") (pintype "passive"))
      (node (ref "C33") (pin "1") (pinfunction "1_1") (pintype "passive"))
      (node (ref "C34") (pin "1") (pinfunction "1_1") (pintype "passive"))
      (node (ref "C4") (pin "2") (pinfunction "2_2") (pintype "passive"))
      (node (ref "C5") (pin "2") (pinfunction "2_2") (pintype "passive"))
      (node (ref "C6") (pin "1") (pinfunction "1_1") (pintype "passive"))
      (node (ref "C8") (pin "2") (pinfunction "2_2") (pintype "passive"))
      (node (ref "C9") (pin "2") (pinfunction "2_2") (pintype "passive"))
      (node (ref "D2") (pin "2") (pinfunction "ANODE_2") (pintype "passive"))
      (node (ref "GND") (pin "1") (pinfunction "P_1") (pintype "passive"))
      (node (ref "J1") (pin "3") (pinfunction "OUT_3") (pintype "bidirectional"))
      (node (ref "J1") (pin "4") (pinfunction "OUT_4") (pintype "bidirectional"))
      (node (ref "J2") (pin "A1/B12") (pinfunction "GND_A1/B12") (pintype "power_in"))
      (node (ref "J2") (pin "B1/A12") (pinfunction "GND_B1/A12") (pintype "power_in"))
      (node (ref "J2") (pin "S1") (pinfunction "GND_S1") (pintype "power_in"))
      (node (ref "J2") (pin "S2") (pinfunction "GND_S2") (pintype "power_in"))
      (node (ref "J2") (pin "S3") (pinfunction "GND_S3") (pintype "power_in"))
      (node (ref "J2") (pin "S4") (pinfunction "GND_S4") (pintype "power_in"))
      (node (ref "J3") (pin "GND@0") (pinfunction "GND_GND@0") (pintype "bidirectional"))
      (node (ref "J3") (pin "GND@1") (pinfunction "GND_GND@1") (pintype "bidirectional"))
      (node (ref "J3") (pin "GND@2") (pinfunction "GND_GND@2") (pintype "bidirectional"))
      (node (ref "J3") (pin "GND@3") (pinfunction "GND_GND@3") (pintype "bidirectional"))
      (node (ref "P1") (pin "3") (pinfunction "GND_3") (pintype "passive"))
      (node (ref "P1") (pin "5") (pinfunction "GND_5") (pintype "passive"))
      (node (ref "P1") (pin "9") (pinfunction "GND_9") (pintype "passive"))
      (node (ref "R10") (pin "1") (pinfunction "1_1") (pintype "passive"))
      (node (ref "R11") (pin "1") (pinfunction "1_1") (pintype "passive"))
      (node (ref "R2") (pin "2") (pinfunction "2_2") (pintype "passive"))
      (node (ref "R5") (pin "1") (pinfunction "1_1") (pintype "passive"))
      (node (ref "R6") (pin "1") (pinfunction "1_1") (pintype "passive"))
      (node (ref "R8") (pin "1") (pinfunction "1_1") (pintype "passive"))
      (node (ref "U1") (pin "0") (pinfunction "VSS_0") (pintype "power_in"))
      (node (ref "U1") (pin "14") (pinfunction "VSS_14") (pintype "power_in"))
      (node (ref "U1") (pin "17") (pinfunction "VSS_17") (pintype "power_in"))
      (node (ref "U1") (pin "20") (pinfunction "VSS_20") (pintype "power_in"))
      (node (ref "U1") (pin "8") (pinfunction "VSS_8") (pintype "power_in"))
      (node (ref "U10") (pin "1") (pinfunction "GND_1") (pintype "power_in"))
      (node (ref "U10") (pin "3") (pinfunction "GND_3") (pintype "power_in"))
      (node (ref "U10") (pin "4") (pinfunction "GND_4") (pintype "power_in"))
      (node (ref "U10") (pin "6") (pinfunction "GND_6") (pintype "power_in"))
      (node (ref "U2") (pin "4") (pinfunction "GND_4") (pintype "bidirectional"))
      (node (ref "U2") (pin "7") (pinfunction "TEST_7") (pintype "bidirectional"))
      (node (ref "U3") (pin "17") (pinfunction "GND_17") (pintype "power_in"))
      (node (ref "U3") (pin "20") (pinfunction "GND_20") (pintype "power_in"))
      (node (ref "U3") (pin "24") (pinfunction "AGND_24") (pintype "power_in"))
      (node (ref "U3") (pin "26") (pinfunction "TEST_26") (pintype "input"))
      (node (ref "U3") (pin "33") (pinfunction "EXP_33") (pintype "power_in"))
      (node (ref "U3") (pin "4") (pinfunction "GND_4") (pintype "power_in"))
      (node (ref "U4") (pin "3") (pinfunction "PG_3") (pintype "bidirectional"))
      (node (ref "U4") (pin "5") (pinfunction "GND_5") (pintype "bidirectional"))
      (node (ref "U5") (pin "7") (pinfunction "GND_7") (pintype "power_in"))
      (node (ref "U5") (pin "9") (pinfunction "EPAD_9") (pintype "bidirectional"))
      (node (ref "U6") (pin "11") (pinfunction "GND_11") (pintype "power_in"))
      (node (ref "U6") (pin "17") (pinfunction "GND_17") (pintype "power_in"))
      (node (ref "U6") (pin "2") (pinfunction "GND_2") (pintype "power_in"))
      (node (ref "U6") (pin "3") (pinfunction "GND_3") (pintype "power_in"))
      (node (ref "U6") (pin "8") (pinfunction "GND_8") (pintype "power_in"))
      (node (ref "U6") (pin "9") (pinfunction "GND_9") (pintype "power_in"))
      (node (ref "U7") (pin "P$3") (pinfunction "GND_P$3") (pintype "power_in"))
      (node (ref "U8") (pin "12") (pinfunction "VSSA/VREF-_12") (pintype "bidirectional"))
      (node (ref "U8") (pin "18") (pinfunction "VSS0_18") (pintype "bidirectional"))
      (node (ref "U8") (pin "31") (pinfunction "VSS1_31") (pintype "bidirectional"))
      (node (ref "U8") (pin "47") (pinfunction "VSS2_47") (pintype "bidirectional"))
      (node (ref "U8") (pin "63") (pinfunction "VSS3_63") (pintype "bidirectional"))
      (node (ref "U9") (pin "11") (pinfunction "FSYNC_11") (pintype "input"))
      (node (ref "U9") (pin "18") (pinfunction "GND_18") (pintype "power_in"))
      (node (ref "U9") (pin "20") (pinfunction "RESV_20_20") (pintype "passive"))
      (node (ref "U9") (pin "9") (pinfunction "AD0/SDO_9") (pintype "bidirectional"))
      (node (ref "X3") (pin "2") (pinfunction "GND_2") (pintype "power_in"))
      (node (ref "X3") (pin "4") (pinfunction "GND_4") (pintype "power_in"))
    )
    (net (code "8") (name "IMU_IRQ") (class "Default")
      (node (ref "U8") (pin "41") (pinfunction "PA8_41") (pintype "bidirectional"))
      (node (ref "U9") (pin "12") (pinfunction "INT1_12") (pintype "output"))
    )
    (net (code "9") (name "LED_SDO") (class "Default")
      (node (ref "TP9") (pin "TP") (pinfunction "TP_TP") (pintype "input"))
      (node (ref "U2") (pin "6") (pinfunction "SDI_6") (pintype "bidirectional"))
      (node (ref "U8") (pin "21") (pinfunction "PA5_21") (pintype "bidirectional"))
    )
    (net (code "10") (name "MOTOR1") (class "Default")
      (node (ref "ESC1") (pin "1") (pinfunction "P_1") (pintype "passive"))
      (node (ref "U8") (pin "22") (pinfunction "PA6_22") (pintype "bidirectional"))
    )
    (net (code "11") (name "MOTOR2") (class "Default")
      (node (ref "ESC2") (pin "1") (pinfunction "P_1") (pintype "passive"))
      (node (ref "U8") (pin "23") (pinfunction "PA7_23") (pintype "bidirectional"))
    )
    (net (code "12") (name "MOTOR3") (class "Default")
      (node (ref "ESC3") (pin "1") (pinfunction "P_1") (pintype "passive"))
      (node (ref "U8") (pin "26") (pinfunction "PB0_26") (pintype "bidirectional"))
    )
    (net (code "13") (name "MOTOR4") (class "Default")
      (node (ref "ESC4") (pin "1") (pinfunction "P_1") (pintype "passive"))
      (node (ref "U8") (pin "27") (pinfunction "PB1_27") (pintype "bidirectional"))
    )
    (net (code "14") (name "NRST") (class "Default")
      (node (ref "C17") (pin "2") (pinfunction "2_2") (pintype "passive"))
      (node (ref "J1") (pin "1") (pinfunction "IN_1") (pintype "bidirectional"))
      (node (ref "J1") (pin "2") (pinfunction "IN_2") (pintype "bidirectional"))
      (node (ref "P1") (pin "10") (pinfunction "RESETN_10") (pintype "passive"))
      (node (ref "R9") (pin "1") (pinfunction "1_1") (pintype "passive"))
      (node (ref "U8") (pin "7") (pinfunction "NRST_7") (pintype "bidirectional"))
    )
    (net (code "15") (name "Net-(C7-Pad1)") (class "Default")
      (node (ref "C7") (pin "1") (pinfunction "1_1") (pintype "passive"))
      (node (ref "L3") (pin "2") (pinfunction "2_2") (pintype "passive"))
    )
    (net (code "16") (name "Net-(D1-BLUE_CATHODE)") (class "Default")
      (node (ref "D1") (pin "3") (pinfunction "BLUE_CATHODE_3") (pintype "passive"))
      (node (ref "U2") (pin "1") (pinfunction "OUT0_1") (pintype "bidirectional"))
    )
    (net (code "17") (name "Net-(D1-GREEN_CATHODE)") (class "Default")
      (node (ref "D1") (pin "2") (pinfunction "GREEN_CATHODE_2") (pintype "passive"))
      (node (ref "U2") (pin "2") (pinfunction "OUT1_2") (pintype "bidirectional"))
    )
    (net (code "18") (name "Net-(D1-RED_CATHODE)") (class "Default")
      (node (ref "D1") (pin "1") (pinfunction "RED_CATHODE_1") (pintype "passive"))
      (node (ref "U2") (pin "3") (pinfunction "OUT2_3") (pintype "bidirectional"))
    )
    (net (code "19") (name "Net-(D2-CATHODE)") (class "Default")
      (node (ref "C19") (pin "2") (pinfunction "2_2") (pintype "passive"))
      (node (ref "D2") (pin "1") (pinfunction "CATHODE_1") (pintype "passive"))
      (node (ref "L4") (pin "@1") (pinfunction "1_@1") (pintype "passive"))
      (node (ref "U5") (pin "8") (pinfunction "SW_8") (pintype "output"))
    )
    (net (code "20") (name "Net-(J2-CC1)") (class "Default")
      (node (ref "J2") (pin "A5") (pinfunction "CC1_A5") (pintype "bidirectional"))
      (node (ref "R11") (pin "2") (pinfunction "2_2") (pintype "passive"))
    )
    (net (code "21") (name "Net-(J2-CC2)") (class "Default")
      (node (ref "J2") (pin "B5") (pinfunction "CC2_B5") (pintype "bidirectional"))
      (node (ref "R8") (pin "2") (pinfunction "2_2") (pintype "passive"))
    )
    (net (code "22") (name "Net-(J3-SIGNAL)") (class "Default")
      (node (ref "J3") (pin "SIG") (pinfunction "SIGNAL_SIG") (pintype "bidirectional"))
      (node (ref "U10") (pin "5") (pinfunction "OUT_5") (pintype "output"))
    )
    (net (code "23") (name "Net-(LED1-PadC)") (class "Default")
      (node (ref "LED1") (pin "C") (pinfunction "C_C") (pintype "passive"))
      (node (ref "R6") (pin "2") (pinfunction "2_2") (pintype "passive"))
    )
    (net (code "24") (name "Net-(Q2-S)") (class "Default")
      (node (ref "D4") (pin "C") (pinfunction "C_C") (pintype "passive"))
      (node (ref "Q2") (pin "P2") (pinfunction "S_P2") (pintype "passive"))
    )
    (net (code "25") (name "Net-(U1-ANT1)") (class "Default")
      (node (ref "L1") (pin "1") (pinfunction "1_1") (pintype "passive"))
      (node (ref "L2") (pin "2") (pinfunction "2_2") (pintype "passive"))
      (node (ref "U1") (pin "12") (pinfunction "ANT1_12") (pintype "output"))
    )
    (net (code "26") (name "Net-(U1-ANT2)") (class "Default")
      (node (ref "L1") (pin "2") (pinfunction "2_2") (pintype "passive"))
      (node (ref "L3") (pin "1") (pinfunction "1_1") (pintype "passive"))
      (node (ref "U1") (pin "13") (pinfunction "ANT2_13") (pintype "output"))
    )
    (net (code "27") (name "Net-(U1-DVDD)") (class "Default")
      (node (ref "C3") (pin "1") (pinfunction "1_1") (pintype "passive"))
      (node (ref "U1") (pin "19") (pinfunction "DVDD_19") (pintype "power_in"))
    )
    (net (code "28") (name "Net-(U1-IREF)") (class "Default")
      (node (ref "R2") (pin "1") (pinfunction "1_1") (pintype "passive"))
      (node (ref "U1") (pin "16") (pinfunction "IREF_16") (pintype "input"))
    )
    (net (code "29") (name "Net-(U1-XC1)") (class "Default")
      (node (ref "C2") (pin "1") (pinfunction "1_1") (pintype "passive"))
      (node (ref "R1") (pin "2") (pinfunction "2_2") (pintype "passive"))
      (node (ref "U1") (pin "10") (pinfunction "XC1_10") (pintype "input"))
      (node (ref "X3") (pin "3") (pinfunction "3_3") (pintype "passive"))
    )
    (net (code "30") (name "Net-(U1-XC2)") (class "Default")
      (node (ref "C1") (pin "1") (pinfunction "1_1") (pintype "passive"))
      (node (ref "R1") (pin "1") (pinfunction "1_1") (pintype "passive"))
      (node (ref "U1") (pin "9") (pinfunction "XC2_9") (pintype "input"))
      (node (ref "X3") (pin "1") (pinfunction "1_1") (pintype "passive"))
    )
    (net (code "31") (name "Net-(U5-BST)") (class "Default")
      (node (ref "C19") (pin "1") (pinfunction "1_1") (pintype "passive"))
      (node (ref "U5") (pin "1") (pinfunction "BST_1") (pintype "power_in"))
    )
    (net (code "32") (name "Net-(U5-PGOOD)") (class "Default")
      (node (ref "R7") (pin "2") (pinfunction "2_2") (pintype "passive"))
      (node (ref "U5") (pin "4") (pinfunction "PGOOD_4") (pintype "output"))
    )
    (net (code "33") (name "Net-(U6-RXEN)") (class "Default")
      (node (ref "R16") (pin "1") (pinfunction "1_1") (pintype "passive"))
      (node (ref "U6") (pin "6") (pinfunction "RXEN_6") (pintype "input"))
    )
    (net (code "34") (name "Net-(U6-TXEN)") (class "Default")
      (node (ref "R15") (pin "1") (pinfunction "1_1") (pintype "passive"))
      (node (ref "U6") (pin "5") (pinfunction "TXEN_5") (pintype "input"))
    )
    (net (code "35") (name "Net-(U7-CAP)") (class "Default")
      (node (ref "C13") (pin "1") (pinfunction "1_1") (pintype "passive"))
      (node (ref "U7") (pin "P$2") (pinfunction "CAP_P$2") (pintype "passive"))
    )
    (net (code "36") (name "Net-(U8-BOOT0)") (class "Default")
      (node (ref "R5") (pin "2") (pinfunction "2_2") (pintype "passive"))
      (node (ref "U8") (pin "60") (pinfunction "BOOT0_60") (pintype "bidirectional"))
    )
    (net (code "37") (name "Net-(U8-PC14-OSC32_IN)") (class "Default")
      (node (ref "C11") (pin "1") (pinfunction "1_1") (pintype "passive"))
      (node (ref "U8") (pin "3") (pinfunction "PC14-OSC32_IN_3") (pintype "bidirectional"))
      (node (ref "X2") (pin "1") (pinfunction "1_1") (pintype "bidirectional"))
    )
    (net (code "38") (name "Net-(U8-PC15-OSC32_OUT)") (class "Default")
      (node (ref "C10") (pin "1") (pinfunction "1_1") (pintype "passive"))
      (node (ref "U8") (pin "4") (pinfunction "PC15-OSC32_OUT_4") (pintype "bidirectional"))
      (node (ref "X2") (pin "2") (pinfunction "2_2") (pintype "bidirectional"))
    )
    (net (code "39") (name "Net-(U8-PH0-OSC_IN)") (class "Default")
      (node (ref "C9") (pin "1") (pinfunction "1_1") (pintype "passive"))
      (node (ref "U8") (pin "5") (pinfunction "PH0-OSC_IN_5") (pintype "bidirectional"))
      (node (ref "X1") (pin "1") (pinfunction "P$1_1") (pintype "bidirectional"))
    )
    (net (code "40") (name "Net-(U8-PH0-OSC_OUT)") (class "Default")
      (node (ref "C8") (pin "1") (pinfunction "1_1") (pintype "passive"))
      (node (ref "U8") (pin "6") (pinfunction "PH0-OSC_OUT_6") (pintype "bidirectional"))
      (node (ref "X1") (pin "2") (pinfunction "P$2_2") (pintype "bidirectional"))
    )
    (net (code "41") (name "Net-(U8-VCAP_1)") (class "Default")
      (node (ref "C14") (pin "2") (pinfunction "2_2") (pintype "passive"))
      (node (ref "U8") (pin "30") (pinfunction "VCAP_1_30") (pintype "bidirectional"))
    )
    (net (code "42") (name "Net-(U9-REGOUT)") (class "Default")
      (node (ref "C15") (pin "1") (pinfunction "1_1") (pintype "passive"))
      (node (ref "U9") (pin "10") (pinfunction "REGOUT_10") (pintype "output"))
    )
    (net (code "43") (name "Net-(U10-IN)") (class "Default")
      (node (ref "C32") (pin "1") (pinfunction "1_1") (pintype "passive"))
      (node (ref "U10") (pin "2") (pinfunction "IN_2") (pintype "input"))
      (node (ref "U6") (pin "10") (pinfunction "ANT_10") (pintype "passive"))
    )
    (net (code "44") (name "PC0") (class "Default")
      (node (ref "U8") (pin "8") (pinfunction "PC0_8") (pintype "bidirectional"))
    )
    (net (code "45") (name "PC1") (class "Default")
      (node (ref "U8") (pin "9") (pinfunction "PC1_9") (pintype "bidirectional"))
    )
    (net (code "46") (name "PC2") (class "Default")
      (node (ref "U8") (pin "10") (pinfunction "PC2_10") (pintype "bidirectional"))
    )
    (net (code "47") (name "PC3") (class "Default")
      (node (ref "U8") (pin "11") (pinfunction "PC3_11") (pintype "bidirectional"))
    )
    (net (code "48") (name "PC4") (class "Default")
      (node (ref "U8") (pin "24") (pinfunction "PC4_24") (pintype "bidirectional"))
    )
    (net (code "49") (name "PC5") (class "Default")
      (node (ref "U8") (pin "25") (pinfunction "PC5_25") (pintype "bidirectional"))
    )
    (net (code "50") (name "PC7") (class "Default")
      (node (ref "U8") (pin "38") (pinfunction "PC7_38") (pintype "bidirectional"))
    )
    (net (code "51") (name "PC8") (class "Default")
      (node (ref "U8") (pin "39") (pinfunction "PC8_39") (pintype "bidirectional"))
    )
    (net (code "52") (name "PC9") (class "Default")
      (node (ref "U8") (pin "40") (pinfunction "PC9_40") (pintype "bidirectional"))
    )
    (net (code "53") (name "PC10") (class "Default")
      (node (ref "U8") (pin "51") (pinfunction "PC10_51") (pintype "bidirectional"))
    )
    (net (code "54") (name "PC11") (class "Default")
      (node (ref "U8") (pin "52") (pinfunction "PC11_52") (pintype "bidirectional"))
    )
    (net (code "55") (name "PC12") (class "Default")
      (node (ref "U8") (pin "53") (pinfunction "PC12_53") (pintype "bidirectional"))
    )
    (net (code "56") (name "PC13") (class "Default")
      (node (ref "U8") (pin "2") (pinfunction "PC13_2") (pintype "bidirectional"))
    )
    (net (code "57") (name "RF_CE") (class "Default")
      (node (ref "CE") (pin "TP") (pinfunction "TP_TP") (pintype "input"))
      (node (ref "R16") (pin "2") (pinfunction "2_2") (pintype "passive"))
      (node (ref "U1") (pin "1") (pinfunction "CE_1") (pintype "input"))
      (node (ref "U8") (pin "37") (pinfunction "PC6_37") (pintype "bidirectional"))
    )
    (net (code "58") (name "RF_IRQ") (class "Default")
      (node (ref "IRQ") (pin "TP") (pinfunction "TP_TP") (pintype "input"))
      (node (ref "U1") (pin "6") (pinfunction "IRQ_6") (pintype "output"))
      (node (ref "U8") (pin "29") (pinfunction "PB10_29") (pintype "bidirectional"))
    )
    (net (code "59") (name "RF_MISO") (class "Default")
      (node (ref "MISO") (pin "TP") (pinfunction "TP_TP") (pintype "input"))
      (node (ref "U1") (pin "5") (pinfunction "MISO_5") (pintype "output"))
      (node (ref "U8") (pin "35") (pinfunction "PB14_35") (pintype "bidirectional"))
    )
    (net (code "60") (name "RF_MOSI") (class "Default")
      (node (ref "MOSI") (pin "TP") (pinfunction "TP_TP") (pintype "input"))
      (node (ref "U1") (pin "4") (pinfunction "MOSI_4") (pintype "input"))
      (node (ref "U8") (pin "36") (pinfunction "PB15_36") (pintype "bidirectional"))
    )
    (net (code "61") (name "RF_SCK") (class "Default")
      (node (ref "SCK") (pin "TP") (pinfunction "TP_TP") (pintype "input"))
      (node (ref "U1") (pin "3") (pinfunction "SCK_3") (pintype "input"))
      (node (ref "U8") (pin "34") (pinfunction "PB13_34") (pintype "bidirectional"))
    )
    (net (code "62") (name "RF_SS") (class "Default")
      (node (ref "SS") (pin "TP") (pinfunction "TP_TP") (pintype "input"))
      (node (ref "U1") (pin "2") (pinfunction "CSN_2") (pintype "input"))
      (node (ref "U8") (pin "33") (pinfunction "PB12_33") (pintype "bidirectional"))
    )
    (net (code "63") (name "SENSOR_SCL") (class "Default")
      (node (ref "Q6") (pin "3") (pinfunction "D_3") (pintype "bidirectional"))
      (node (ref "R13") (pin "1") (pinfunction "1_1") (pintype "passive"))
      (node (ref "R3") (pin "1") (pinfunction "1_1") (pintype "passive"))
      (node (ref "U7") (pin "P$8") (pinfunction "SCL_P$8") (pintype "bidirectional"))
      (node (ref "U8") (pin "61") (pinfunction "PB8_61") (pintype "bidirectional"))
    )
    (net (code "64") (name "SENSOR_SCL_LV") (class "Default")
      (node (ref "Q6") (pin "2") (pinfunction "S_2") (pintype "bidirectional"))
      (node (ref "R14") (pin "1") (pinfunction "1_1") (pintype "passive"))
      (node (ref "U9") (pin "23") (pinfunction "SCL/SCLK_23") (pintype "input"))
    )
    (net (code "65") (name "SENSOR_SDA") (class "Default")
      (node (ref "Q3") (pin "3") (pinfunction "D_3") (pintype "bidirectional"))
      (node (ref "R17") (pin "1") (pinfunction "1_1") (pintype "passive"))
      (node (ref "R4") (pin "1") (pinfunction "1_1") (pintype "passive"))
      (node (ref "U7") (pin "P$7") (pinfunction "SDA_P$7") (pintype "bidirectional"))
      (node (ref "U8") (pin "62") (pinfunction "PB9_62") (pintype "bidirectional"))
    )
    (net (code "66") (name "SENSOR_SDA_LV") (class "Default")
      (node (ref "Q3") (pin "2") (pinfunction "S_2") (pintype "bidirectional"))
      (node (ref "R12") (pin "1") (pinfunction "1_1") (pintype "passive"))
      (node (ref "U9") (pin "24") (pinfunction "SDA/SDI_24") (pintype "bidirectional"))
    )
    (net (code "67") (name "SWCLK") (class "Default")
      (node (ref "P1") (pin "4") (pinfunction "SWDCLK_4") (pintype "passive"))
      (node (ref "U8") (pin "49") (pinfunction "PA14_49") (pintype "bidirectional"))
    )
    (net (code "68") (name "SWDIO") (class "Default")
      (node (ref "P1") (pin "2") (pinfunction "SWDIO_2") (pintype "passive"))
      (node (ref "U8") (pin "46") (pinfunction "PA13_46") (pintype "bidirectional"))
    )
    (net (code "69") (name "TXRX") (class "Default")
      (node (ref "C6") (pin "2") (pinfunction "2_2") (pintype "passive"))
      (node (ref "C7") (pin "2") (pinfunction "2_2") (pintype "passive"))
      (node (ref "U6") (pin "4") (pinfunction "TXRX_4") (pintype "bidirectional"))
    )
    (net (code "70") (name "USB_DN") (class "Default")
      (node (ref "J2") (pin "A7") (pinfunction "DN1_A7") (pintype "bidirectional"))
      (node (ref "J2") (pin "B7") (pinfunction "DN2_B7") (pintype "bidirectional"))
      (node (ref "U3") (pin "15") (pinfunction "USBDM_15") (pintype "bidirectional"))
    )
    (net (code "71") (name "USB_DP") (class "Default")
      (node (ref "J2") (pin "A6") (pinfunction "DP1_A6") (pintype "bidirectional"))
      (node (ref "J2") (pin "B6") (pinfunction "DP2_B6") (pintype "bidirectional"))
      (node (ref "U3") (pin "14") (pinfunction "USBDP_14") (pintype "bidirectional"))
    )
    (net (code "72") (name "USB_RX") (class "Default")
      (node (ref "U3") (pin "30") (pinfunction "TXD_30") (pintype "output"))
      (node (ref "U8") (pin "17") (pinfunction "PA3_17") (pintype "bidirectional"))
    )
    (net (code "73") (name "USB_TX") (class "Default")
      (node (ref "U3") (pin "2") (pinfunction "RXD_2") (pintype "input"))
      (node (ref "U8") (pin "16") (pinfunction "PA2_16") (pintype "bidirectional"))
    )
    (net (code "74") (name "USB_VCC") (class "Default")
      (node (ref "D3") (pin "A") (pinfunction "A_A") (pintype "passive"))
      (node (ref "J2") (pin "A4/B9") (pinfunction "VBUS_A4/B9") (pintype "power_in"))
      (node (ref "J2") (pin "B4/A9") (pinfunction "VBUS_B4/A9") (pintype "power_in"))
      (node (ref "JP1") (pin "1") (pinfunction "1_1") (pintype "passive"))
      (node (ref "JP1") (pin "2") (pinfunction "2_2") (pintype "passive"))
      (node (ref "Q2") (pin "P1") (pinfunction "G_P1") (pintype "passive"))
      (node (ref "R10") (pin "2") (pinfunction "2_2") (pintype "passive"))
      (node (ref "USB_VCC") (pin "TP") (pinfunction "TP_TP") (pintype "input"))
    )
    (net (code "75") (name "VDD_PA") (class "Default")
      (node (ref "C4") (pin "1") (pinfunction "1_1") (pintype "passive"))
      (node (ref "C5") (pin "1") (pinfunction "1_1") (pintype "passive"))
      (node (ref "L2") (pin "1") (pinfunction "1_1") (pintype "passive"))
      (node (ref "R15") (pin "2") (pinfunction "2_2") (pintype "passive"))
      (node (ref "U1") (pin "11") (pinfunction "VDD_PA_11") (pintype "power_in"))
    )
    (net (code "76") (name "unconnected-(J2-SBU1-PadA8)") (class "Default")
      (node (ref "J2") (pin "A8") (pinfunction "SBU1_A8") (pintype "bidirectional"))
    )
    (net (code "77") (name "unconnected-(J2-SBU2-PadB8)") (class "Default")
      (node (ref "J2") (pin "B8") (pinfunction "SBU2_B8") (pintype "bidirectional"))
    )
    (net (code "78") (name "unconnected-(P1-NC-Pad7)") (class "Default")
      (node (ref "P1") (pin "7") (pinfunction "NC_7") (pintype "no_connect"))
    )
    (net (code "79") (name "unconnected-(P1-NC-Pad8)") (class "Default")
      (node (ref "P1") (pin "8") (pinfunction "NC_8") (pintype "passive"))
    )
    (net (code "80") (name "unconnected-(P1-SWO-Pad6)") (class "Default")
      (node (ref "P1") (pin "6") (pinfunction "SWO_6") (pintype "passive"))
    )
    (net (code "81") (name "unconnected-(U2-SDO-Pad5)") (class "Default")
      (node (ref "U2") (pin "5") (pinfunction "SDO_5") (pintype "bidirectional"))
    )
    (net (code "82") (name "unconnected-(U3-3V3OUT-Pad16)") (class "Default")
      (node (ref "U3") (pin "16") (pinfunction "3V3OUT_16") (pintype "output"))
    )
    (net (code "83") (name "unconnected-(U3-CBUS0-Pad22)") (class "Default")
      (node (ref "U3") (pin "22") (pinfunction "CBUS0_22") (pintype "bidirectional"))
    )
    (net (code "84") (name "unconnected-(U3-CBUS1-Pad21)") (class "Default")
      (node (ref "U3") (pin "21") (pinfunction "CBUS1_21") (pintype "bidirectional"))
    )
    (net (code "85") (name "unconnected-(U3-CBUS2-Pad10)") (class "Default")
      (node (ref "U3") (pin "10") (pinfunction "CBUS2_10") (pintype "bidirectional"))
    )
    (net (code "86") (name "unconnected-(U3-CBUS3-Pad11)") (class "Default")
      (node (ref "U3") (pin "11") (pinfunction "CBUS3_11") (pintype "bidirectional"))
    )
    (net (code "87") (name "unconnected-(U3-CBUS4-Pad9)") (class "Default")
      (node (ref "U3") (pin "9") (pinfunction "CBUS4_9") (pintype "bidirectional"))
    )
    (net (code "88") (name "unconnected-(U3-OSCI-Pad27)") (class "Default")
      (node (ref "U3") (pin "27") (pinfunction "OSCI_27") (pintype "input"))
    )
    (net (code "89") (name "unconnected-(U3-OSCO-Pad28)") (class "Default")
      (node (ref "U3") (pin "28") (pinfunction "OSCO_28") (pintype "output"))
    )
    (net (code "90") (name "unconnected-(U3-~{CTS}-Pad8)") (class "Default")
      (node (ref "U3") (pin "8") (pinfunction "~{CTS}_8") (pintype "input"))
    )
    (net (code "91") (name "unconnected-(U3-~{DCD}-Pad7)") (class "Default")
      (node (ref "U3") (pin "7") (pinfunction "~{DCD}_7") (pintype "input"))
    )
    (net (code "92") (name "unconnected-(U3-~{DSR}-Pad6)") (class "Default")
      (node (ref "U3") (pin "6") (pinfunction "~{DSR}_6") (pintype "input"))
    )
    (net (code "93") (name "unconnected-(U3-~{DTR}-Pad31)") (class "Default")
      (node (ref "U3") (pin "31") (pinfunction "~{DTR}_31") (pintype "output"))
    )
    (net (code "94") (name "unconnected-(U3-~{RESET}-Pad18)") (class "Default")
      (node (ref "U3") (pin "18") (pinfunction "~{RESET}_18") (pintype "input"))
    )
    (net (code "95") (name "unconnected-(U3-~{RI}-Pad3)") (class "Default")
      (node (ref "U3") (pin "3") (pinfunction "~{RI}_3") (pintype "input"))
    )
    (net (code "96") (name "unconnected-(U3-~{RTS}-Pad32)") (class "Default")
      (node (ref "U3") (pin "32") (pinfunction "~{RTS}_32") (pintype "output"))
    )
    (net (code "97") (name "unconnected-(U4-FB-Pad2)") (class "Default")
      (node (ref "U4") (pin "2") (pinfunction "FB_2") (pintype "bidirectional"))
    )
    (net (code "98") (name "unconnected-(U8-PA0-Pad14)") (class "Default")
      (node (ref "U8") (pin "14") (pinfunction "PA0_14") (pintype "bidirectional"))
    )
    (net (code "99") (name "unconnected-(U8-PA1-Pad15)") (class "Default")
      (node (ref "U8") (pin "15") (pinfunction "PA1_15") (pintype "bidirectional"))
    )
    (net (code "100") (name "unconnected-(U8-PA4-Pad20)") (class "Default")
      (node (ref "U8") (pin "20") (pinfunction "PA4_20") (pintype "bidirectional"))
    )
    (net (code "101") (name "unconnected-(U8-PA11-Pad44)") (class "Default")
      (node (ref "U8") (pin "44") (pinfunction "PA11_44") (pintype "bidirectional"))
    )
    (net (code "102") (name "unconnected-(U8-PA12-Pad45)") (class "Default")
      (node (ref "U8") (pin "45") (pinfunction "PA12_45") (pintype "bidirectional"))
    )
    (net (code "103") (name "unconnected-(U8-PA15-Pad50)") (class "Default")
      (node (ref "U8") (pin "50") (pinfunction "PA15_50") (pintype "bidirectional"))
    )
    (net (code "104") (name "unconnected-(U8-PB2-Pad28)") (class "Default")
      (node (ref "U8") (pin "28") (pinfunction "PB2_28") (pintype "bidirectional"))
    )
    (net (code "105") (name "unconnected-(U8-PB3-Pad55)") (class "Default")
      (node (ref "U8") (pin "55") (pinfunction "PB3_55") (pintype "bidirectional"))
    )
    (net (code "106") (name "unconnected-(U8-PB4-Pad56)") (class "Default")
      (node (ref "U8") (pin "56") (pinfunction "PB4_56") (pintype "bidirectional"))
    )
    (net (code "107") (name "unconnected-(U8-PB5-Pad57)") (class "Default")
      (node (ref "U8") (pin "57") (pinfunction "PB5_57") (pintype "bidirectional"))
    )
    (net (code "108") (name "unconnected-(U8-PB6-Pad58)") (class "Default")
      (node (ref "U8") (pin "58") (pinfunction "PB6_58") (pintype "bidirectional"))
    )
    (net (code "109") (name "unconnected-(U8-PB7-Pad59)") (class "Default")
      (node (ref "U8") (pin "59") (pinfunction "PB7_59") (pintype "bidirectional"))
    )
    (net (code "110") (name "unconnected-(U8-PD2-Pad54)") (class "Default")
      (node (ref "U8") (pin "54") (pinfunction "PD2_54") (pintype "bidirectional"))
    )
    (net (code "111") (name "unconnected-(U9-AUX_CL-Pad7)") (class "Default")
      (node (ref "U9") (pin "7") (pinfunction "AUX_CL_7") (pintype "input"))
    )
    (net (code "112") (name "unconnected-(U9-AUX_DA-Pad21)") (class "Default")
      (node (ref "U9") (pin "21") (pinfunction "AUX_DA_21") (pintype "bidirectional"))
    )
    (net (code "113") (name "unconnected-(U9-NC-Pad1)") (class "Default")
      (node (ref "U9") (pin "1") (pinfunction "NC_1") (pintype "no_connect"))
    )
    (net (code "114") (name "unconnected-(U9-NC-Pad2)") (class "Default")
      (node (ref "U9") (pin "2") (pinfunction "NC_2") (pintype "no_connect"))
    )
    (net (code "115") (name "unconnected-(U9-NC-Pad3)") (class "Default")
      (node (ref "U9") (pin "3") (pinfunction "NC_3") (pintype "no_connect"))
    )
    (net (code "116") (name "unconnected-(U9-NC-Pad4)") (class "Default")
      (node (ref "U9") (pin "4") (pinfunction "NC_4") (pintype "no_connect"))
    )
    (net (code "117") (name "unconnected-(U9-NC-Pad5)") (class "Default")
      (node (ref "U9") (pin "5") (pinfunction "NC_5") (pintype "no_connect"))
    )
    (net (code "118") (name "unconnected-(U9-NC-Pad6)") (class "Default")
      (node (ref "U9") (pin "6") (pinfunction "NC_6") (pintype "no_connect"))
    )
    (net (code "119") (name "unconnected-(U9-NC-Pad14)") (class "Default")
      (node (ref "U9") (pin "14") (pinfunction "NC_14") (pintype "no_connect"))
    )
    (net (code "120") (name "unconnected-(U9-NC-Pad15)") (class "Default")
      (node (ref "U9") (pin "15") (pinfunction "NC_15") (pintype "no_connect"))
    )
    (net (code "121") (name "unconnected-(U9-NC-Pad16)") (class "Default")
      (node (ref "U9") (pin "16") (pinfunction "NC_16") (pintype "no_connect"))
    )
    (net (code "122") (name "unconnected-(U9-NC-Pad17)") (class "Default")
      (node (ref "U9") (pin "17") (pinfunction "NC_17") (pintype "no_connect"))
    )
    (net (code "123") (name "unconnected-(U9-RESV_19-Pad19)") (class "Default")
      (node (ref "U9") (pin "19") (pinfunction "RESV_19_19") (pintype "passive"))
    )
  )
)
